# Inverter_New_2.net
KiCad netlist of a schematic drawn in EAGLE
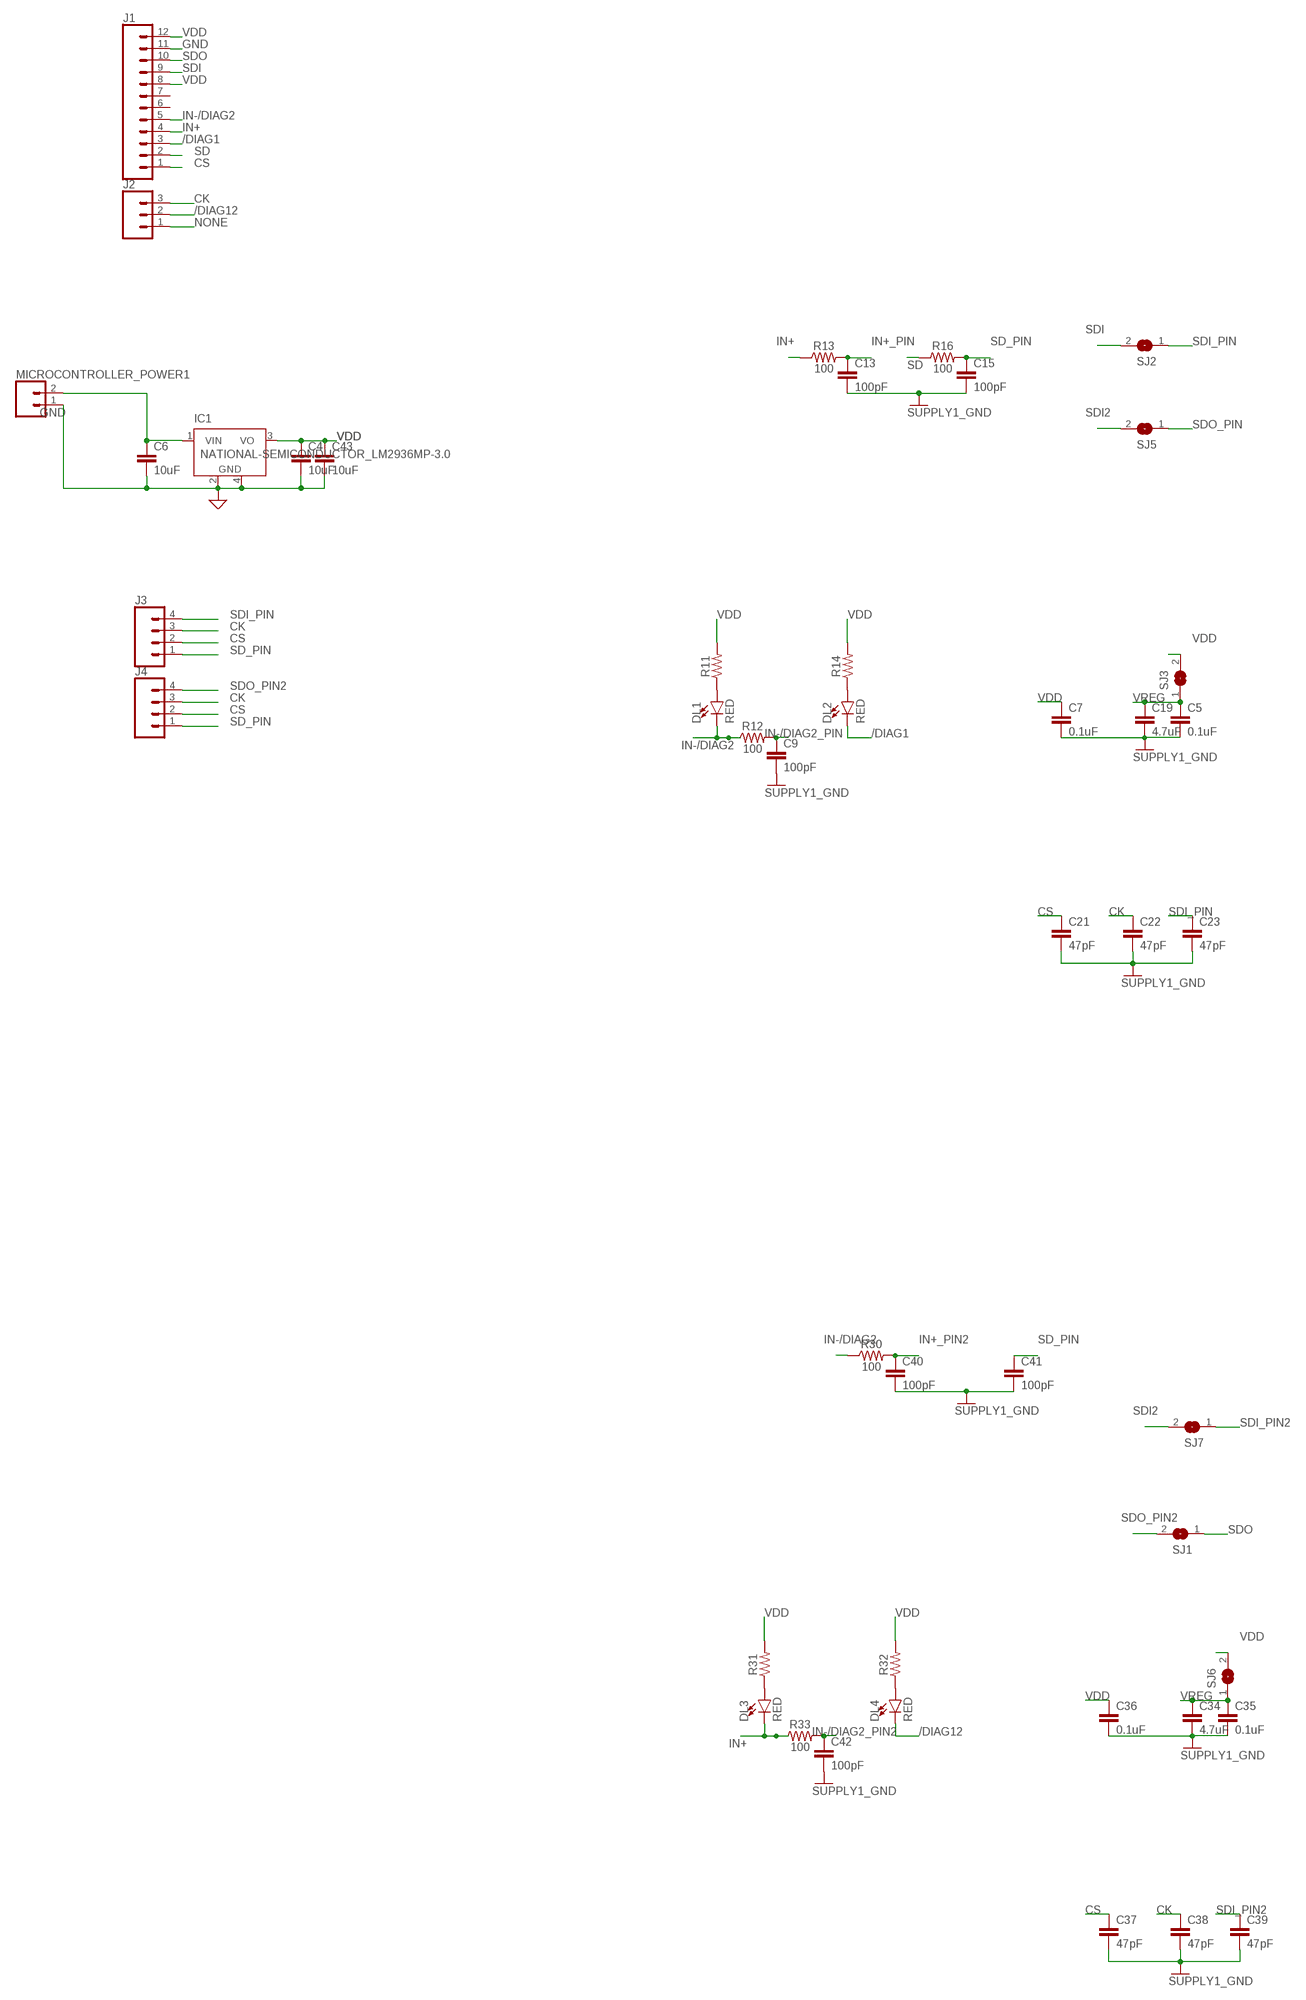
[diagram p0: schematic, sheet 1, part 1 of 2]
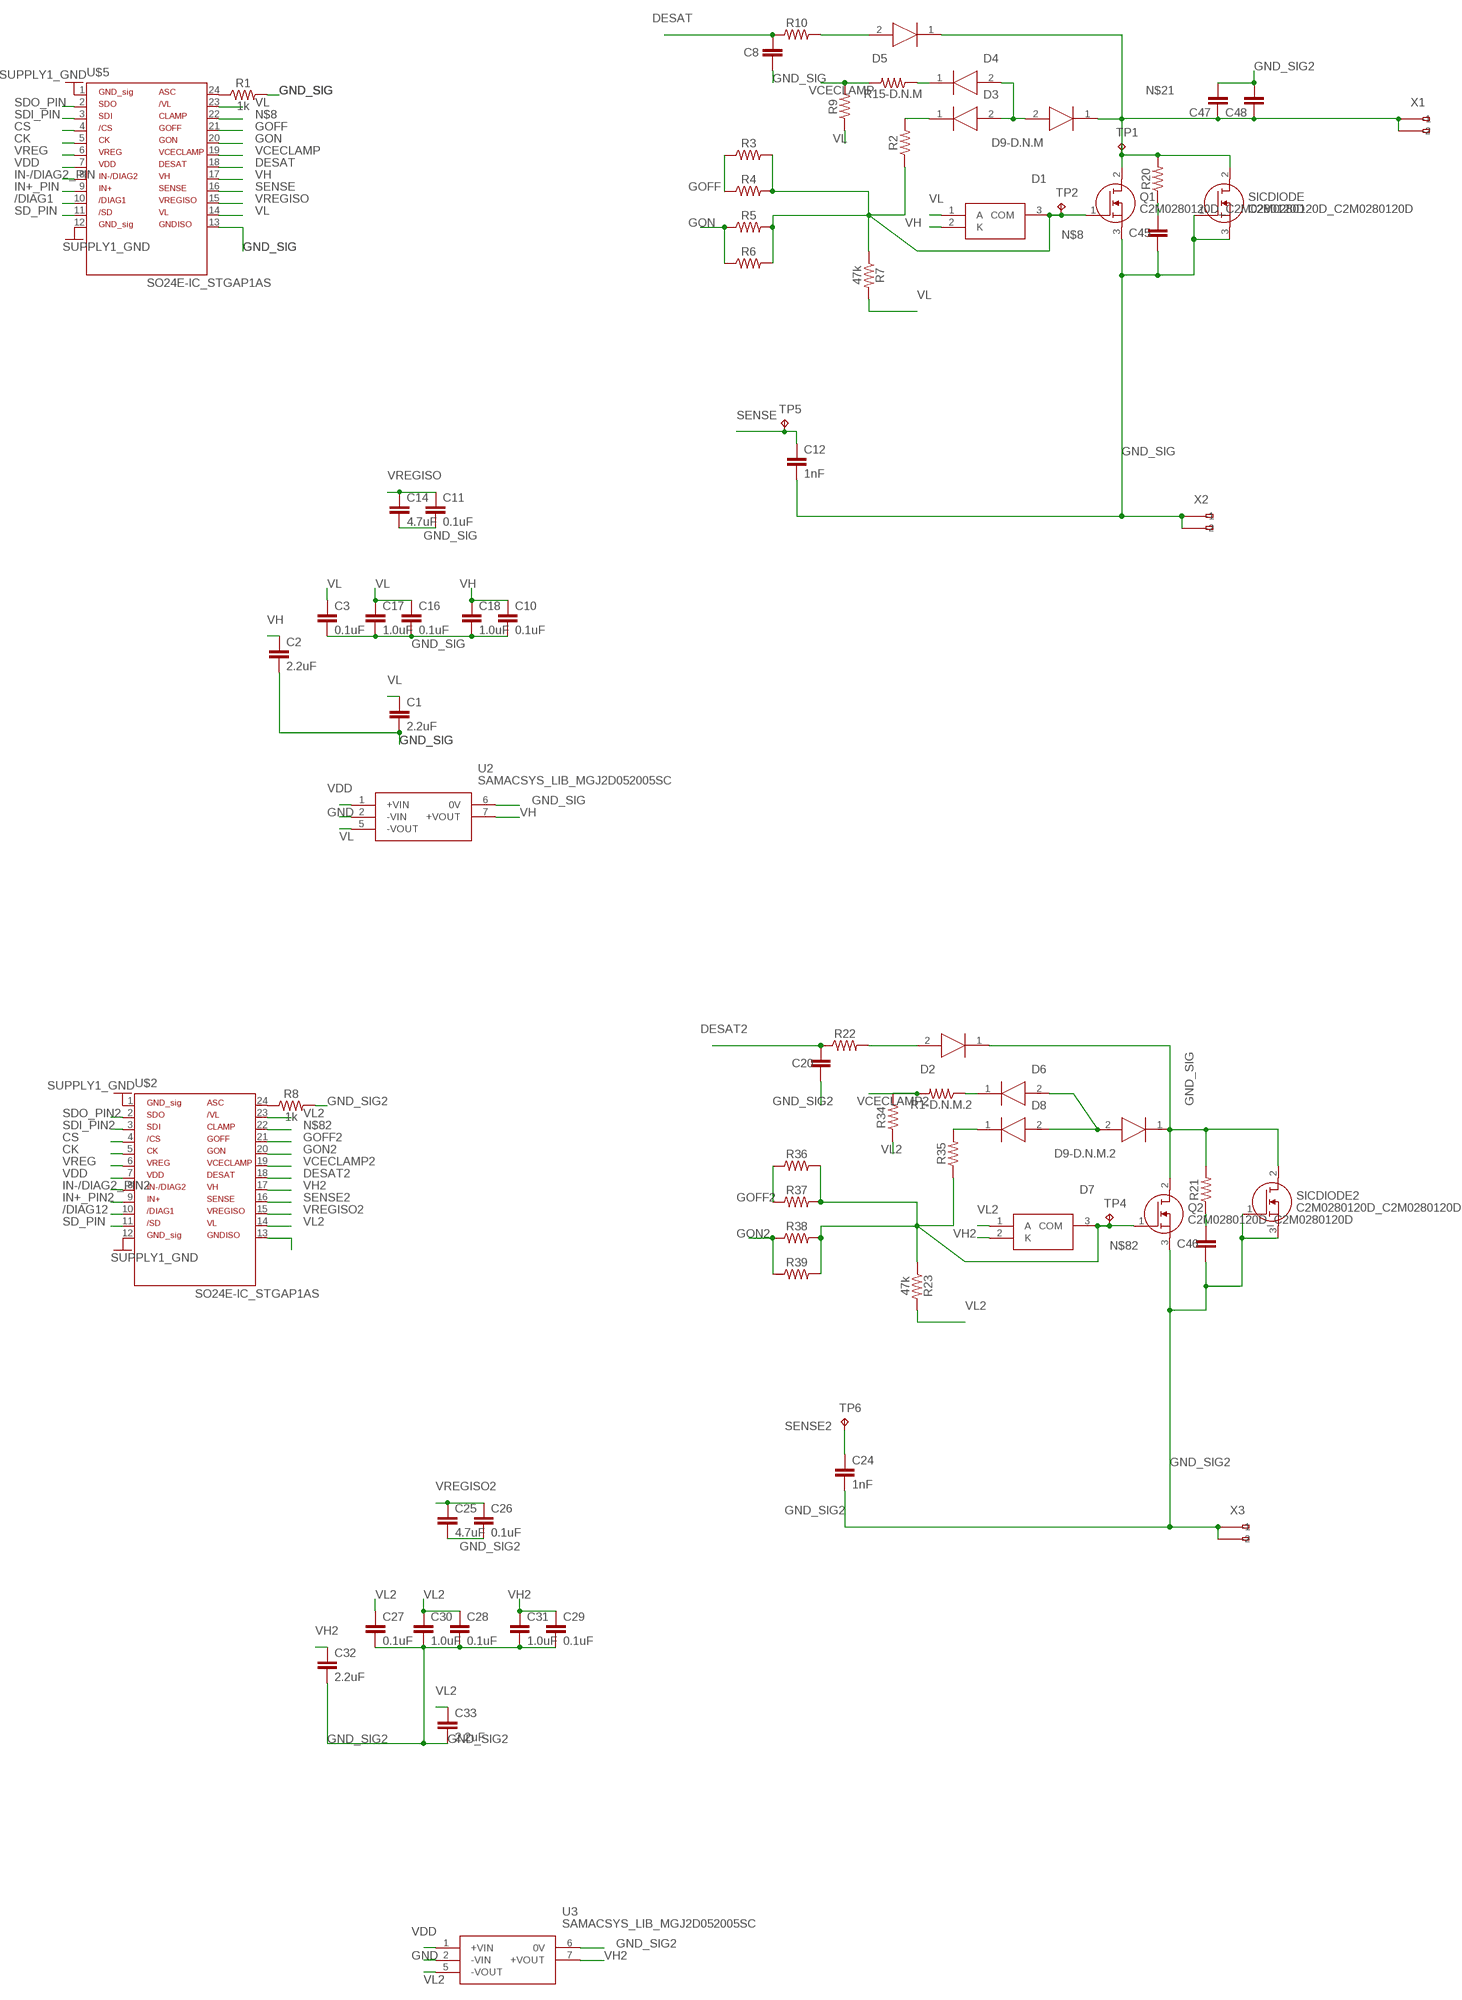
[diagram p1: schematic, sheet 1, part 2 of 2]
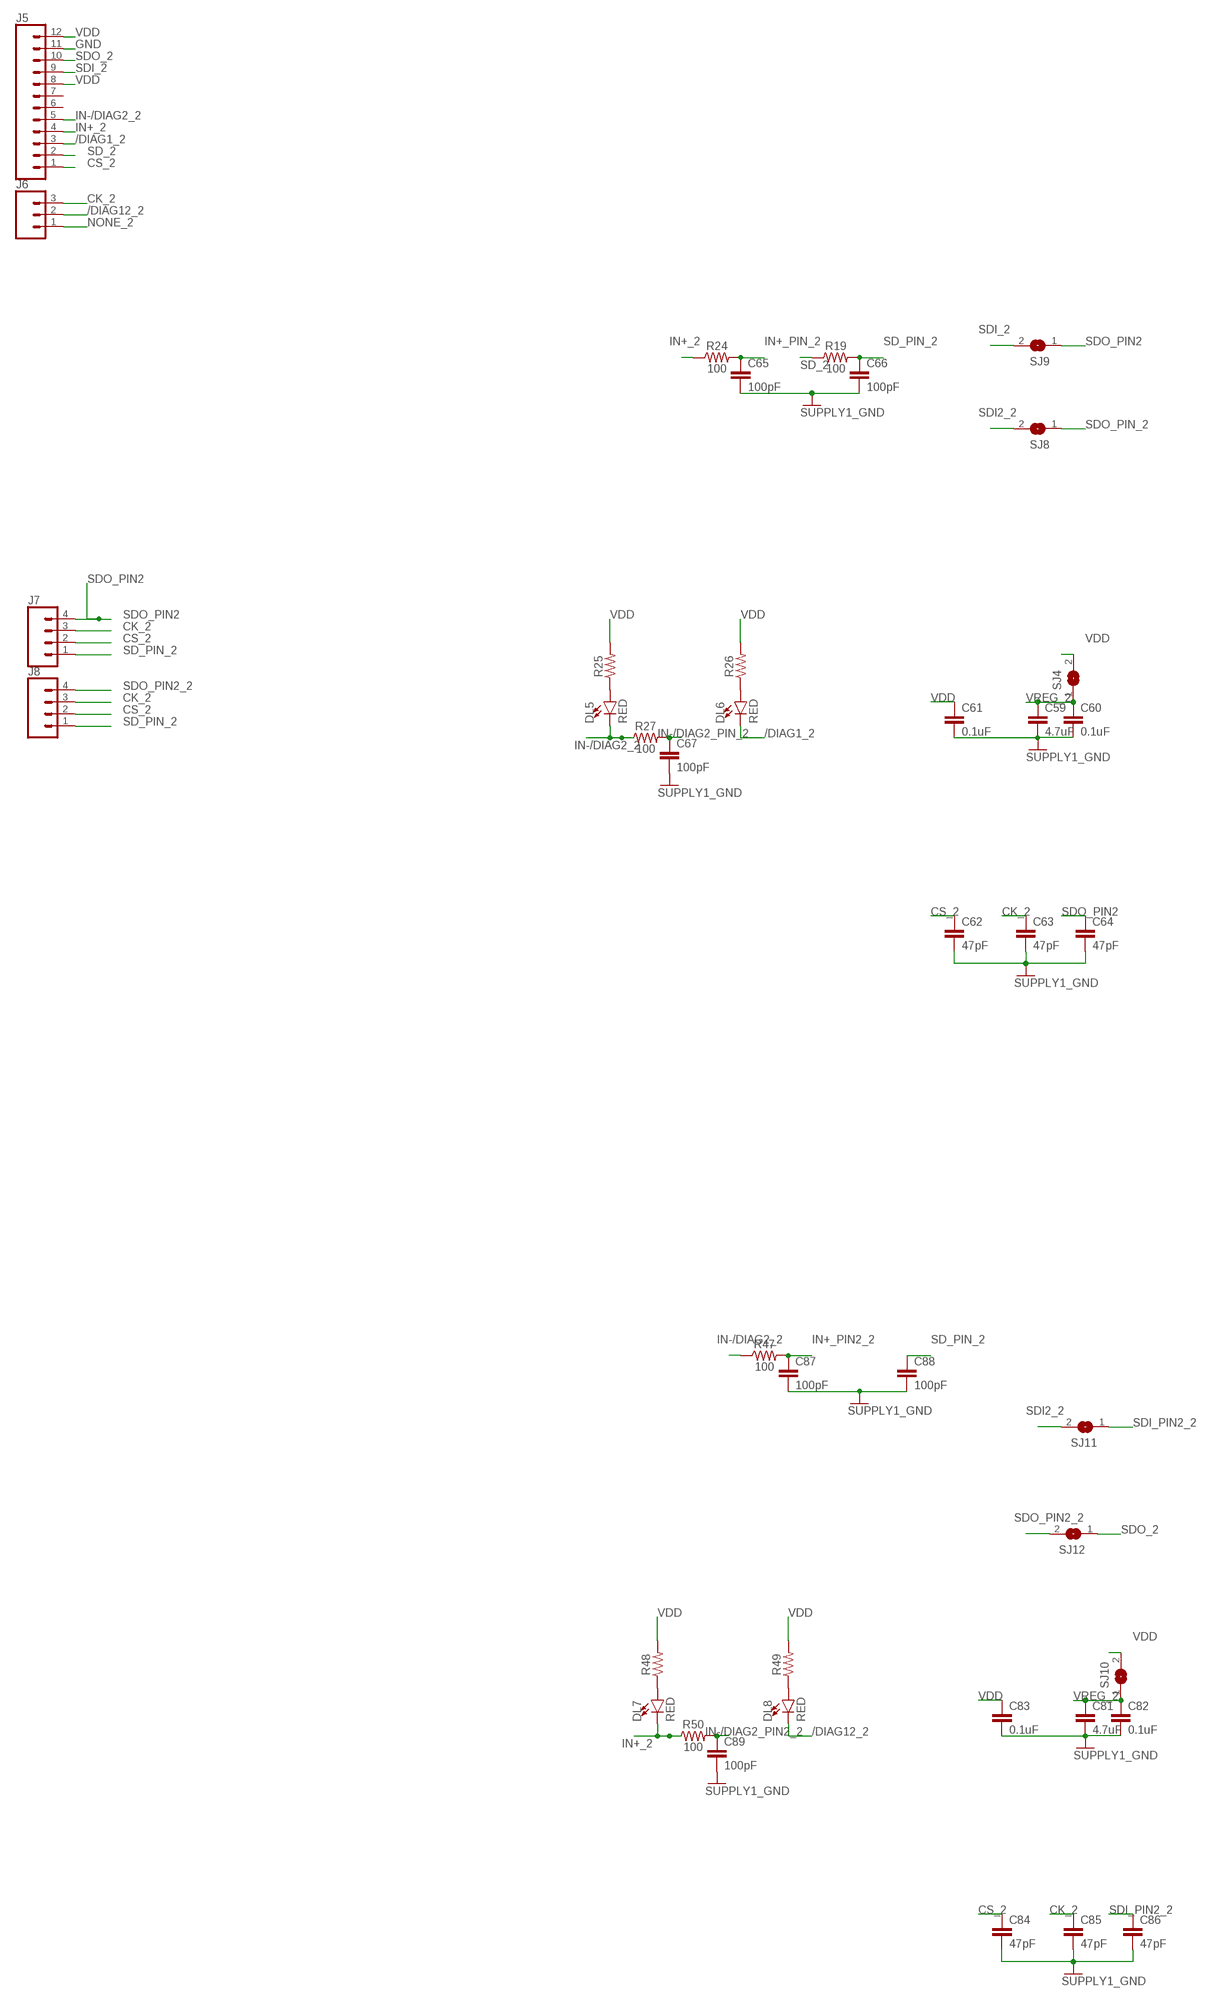
[diagram p2: schematic, sheet 2, part 1 of 2]
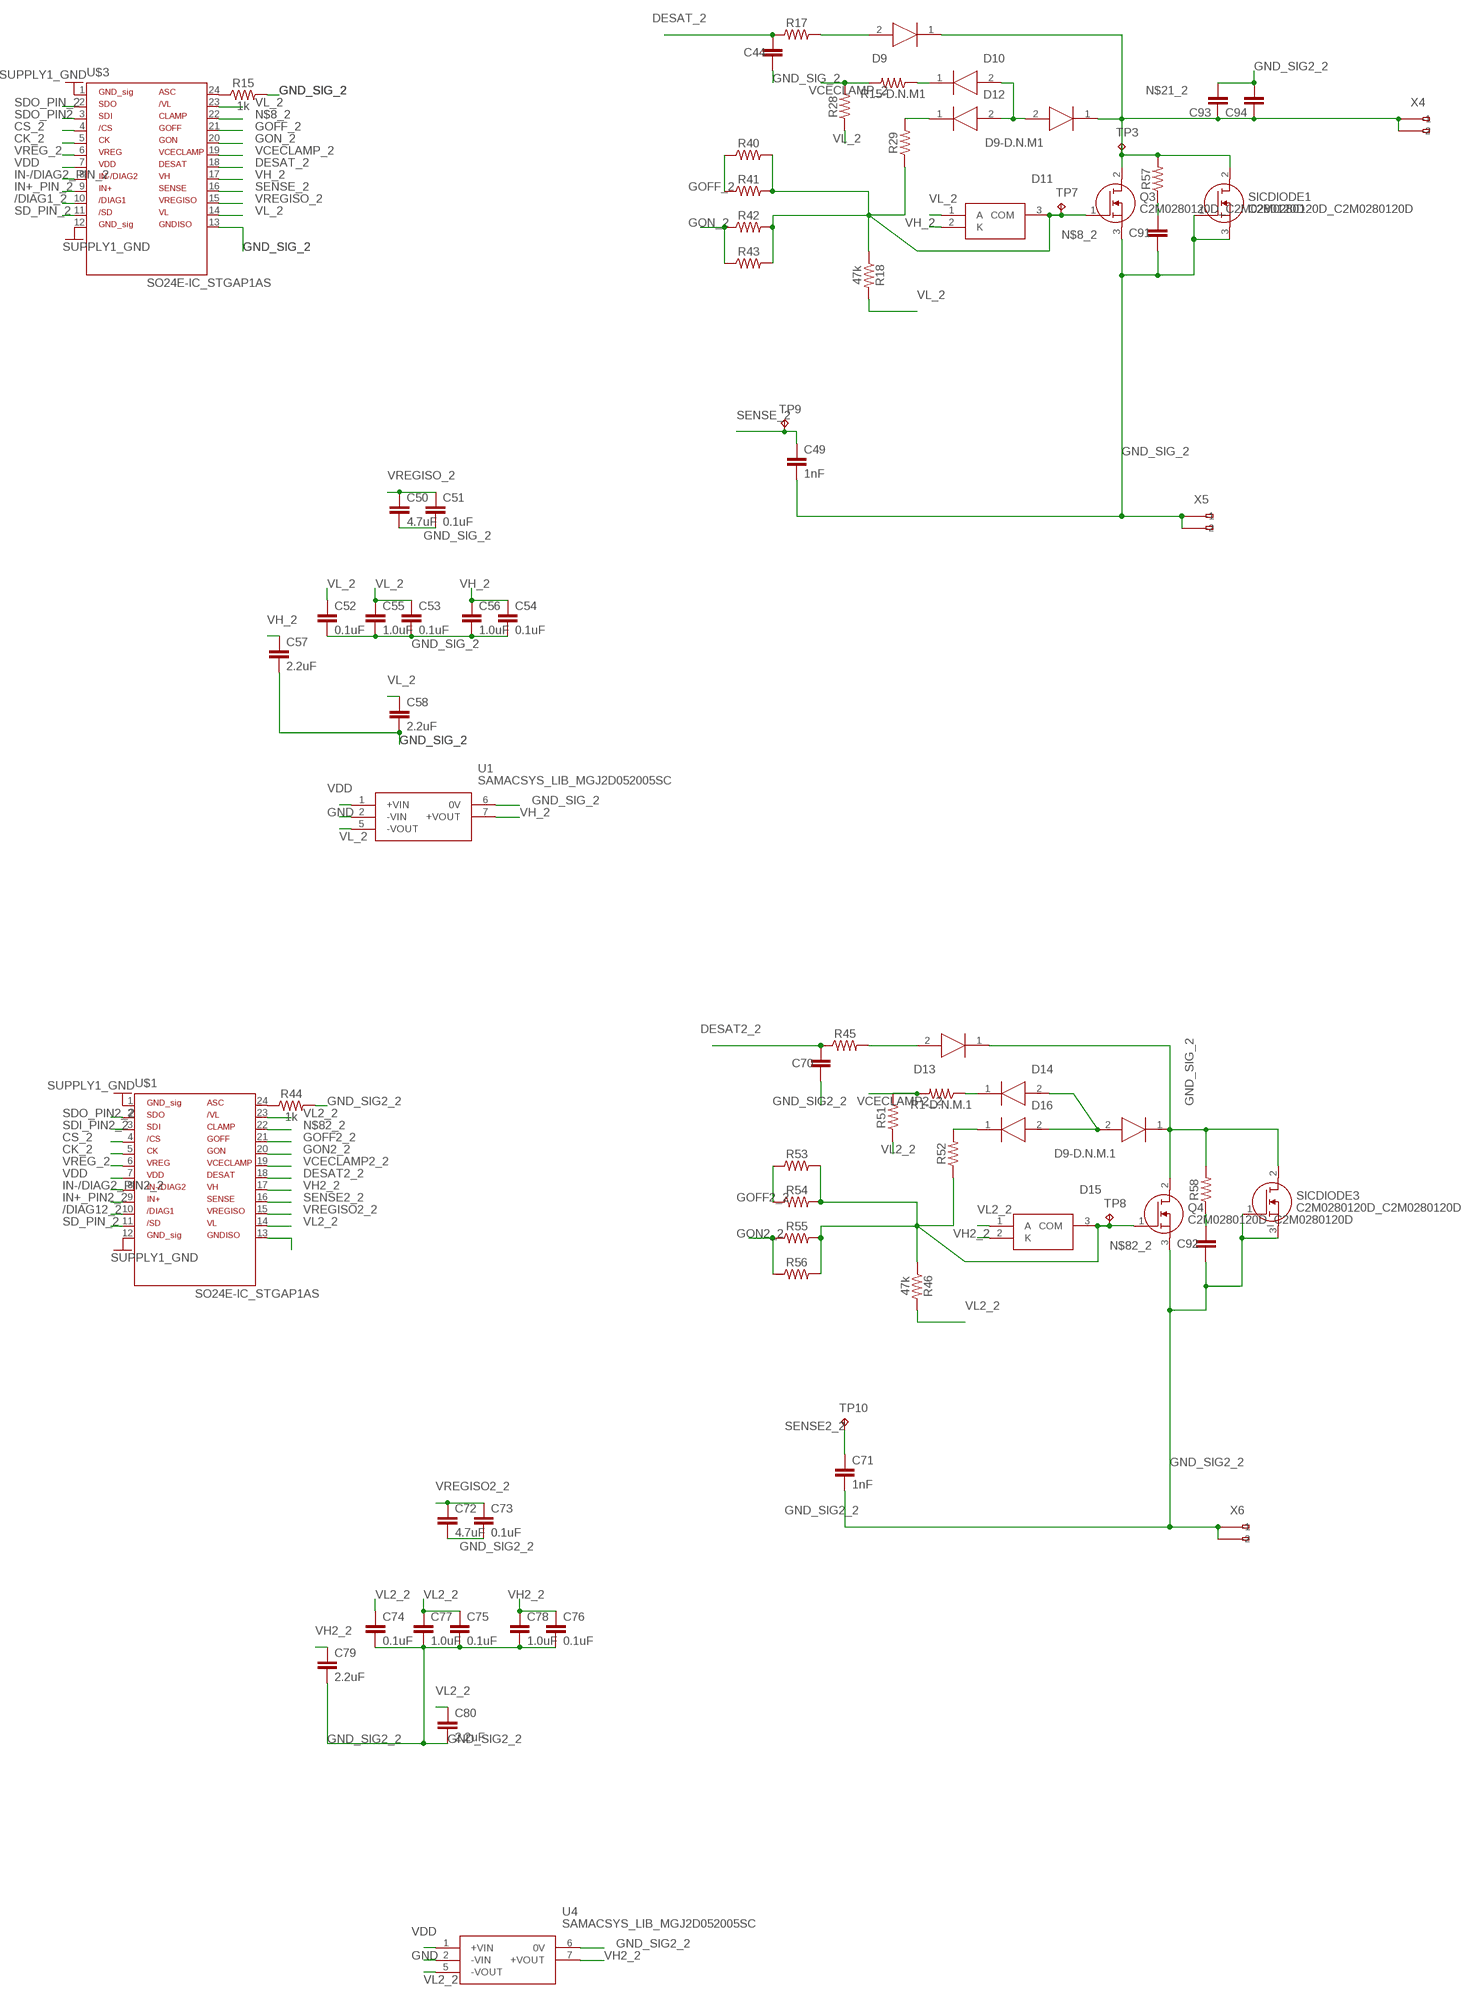
[diagram p3: schematic, sheet 2, part 2 of 2]
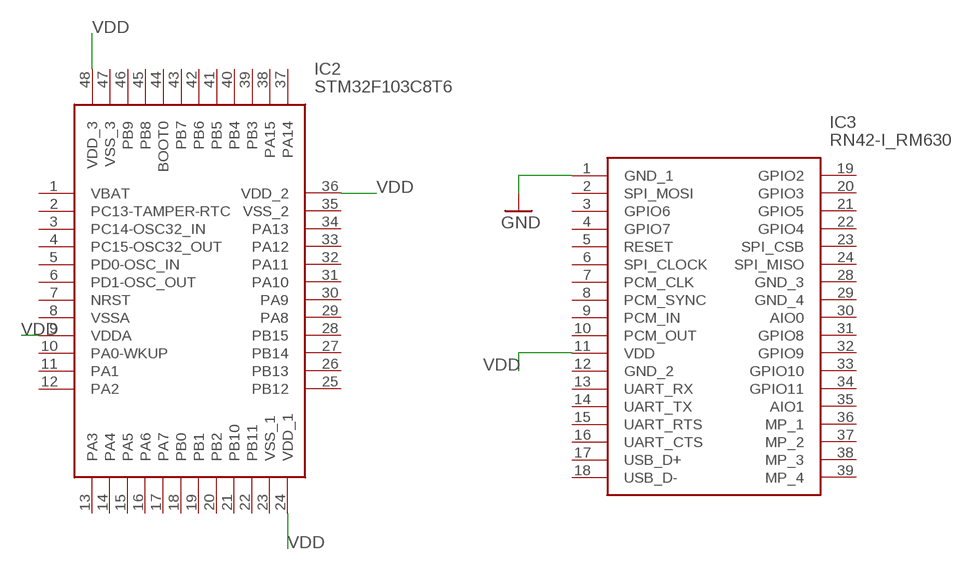
[diagram p4: schematic, sheet 3]

(export (version "E")
  (design (tool "Eeschema 10.0.6"))
  (components
    (comp (ref "IC2")
      (value "STM32F103C8T6")
      (footprint "eagle-import:QFP50P900X900X160-48N")
      (fields
        (field (name "MOUSER_PART_NUMBER") "511-STM32F103C8T6")
        (field (name "RS_PART_NUMBER") "0402279P")
      )
      (libsource (lib "eagle-import") (part "STM32F103C8T6"))
    )
    (comp (ref "IC3")
      (value "RN42-I_RM630")
      (footprint "eagle-import:RN42IRM630")
      (fields
        (field (name "MANUFACTURER_PART_NUMBER") "RN42-I/RM630")
        (field (name "MOUSER_PART_NUMBER") "579-RN42-I/RM630")
        (field (name "RS_PART_NUMBER") "1238533")
      )
      (libsource (lib "eagle-import") (part "RN42-I_RM630"))
    )
    (comp (ref "C44")
      (value "100pF")
      (footprint "eagle-import:SPARKFUN-CAPACITORS_0603")
      (libsource (lib "eagle-import") (part "SPARKFUN-CAPACITORS_100PF-0603-50V-5%"))
    )
    (comp (ref "C49")
      (value "1nF")
      (footprint "eagle-import:SPARKFUN-CAPACITORS_0603")
      (libsource (lib "eagle-import") (part "SPARKFUN-CAPACITORS_1.0NF/1000PF-0603-50V-10%"))
    )
    (comp (ref "C50")
      (value "4.7uF")
      (footprint "eagle-import:SPARKFUN-CAPACITORS_0603")
      (libsource (lib "eagle-import") (part "SPARKFUN-CAPACITORS_4.7UF0603"))
    )
    (comp (ref "C51")
      (value "0.1uF")
      (footprint "eagle-import:SPARKFUN-CAPACITORS_0603")
      (libsource (lib "eagle-import") (part "SPARKFUN-CAPACITORS_0.1UF-0603-100V-10%"))
    )
    (comp (ref "C52")
      (value "0.1uF")
      (footprint "eagle-import:SPARKFUN-CAPACITORS_0603")
      (libsource (lib "eagle-import") (part "SPARKFUN-CAPACITORS_0.1UF-0603-100V-10%"))
    )
    (comp (ref "C53")
      (value "0.1uF")
      (footprint "eagle-import:SPARKFUN-CAPACITORS_0603")
      (libsource (lib "eagle-import") (part "SPARKFUN-CAPACITORS_0.1UF-0603-100V-10%"))
    )
    (comp (ref "C54")
      (value "0.1uF")
      (footprint "eagle-import:SPARKFUN-CAPACITORS_0603")
      (libsource (lib "eagle-import") (part "SPARKFUN-CAPACITORS_0.1UF-0603-100V-10%"))
    )
    (comp (ref "C55")
      (value "1.0uF")
      (footprint "eagle-import:SPARKFUN-CAPACITORS_0805")
      (libsource (lib "eagle-import") (part "SPARKFUN-CAPACITORS_1.0UF-0805-25V-10%"))
    )
    (comp (ref "C56")
      (value "1.0uF")
      (footprint "eagle-import:SPARKFUN-CAPACITORS_0805")
      (libsource (lib "eagle-import") (part "SPARKFUN-CAPACITORS_1.0UF-0805-25V-10%"))
    )
    (comp (ref "C57")
      (value "2.2uF")
      (footprint "eagle-import:SPARKFUN-CAPACITORS_1206")
      (libsource (lib "eagle-import") (part "SPARKFUN-CAPACITORS_2.2UF-1206-50V-10%"))
    )
    (comp (ref "C58")
      (value "2.2uF")
      (footprint "eagle-import:SPARKFUN-CAPACITORS_1206")
      (libsource (lib "eagle-import") (part "SPARKFUN-CAPACITORS_2.2UF-1206-50V-10%"))
    )
    (comp (ref "C59")
      (value "4.7uF")
      (footprint "eagle-import:SPARKFUN-CAPACITORS_0603")
      (libsource (lib "eagle-import") (part "SPARKFUN-CAPACITORS_4.7UF0603"))
    )
    (comp (ref "C60")
      (value "0.1uF")
      (footprint "eagle-import:SPARKFUN-CAPACITORS_0603")
      (libsource (lib "eagle-import") (part "SPARKFUN-CAPACITORS_0.1UF-0603-100V-10%"))
    )
    (comp (ref "C61")
      (value "0.1uF")
      (footprint "eagle-import:SPARKFUN-CAPACITORS_0603")
      (libsource (lib "eagle-import") (part "SPARKFUN-CAPACITORS_0.1UF-0603-100V-10%"))
    )
    (comp (ref "C62")
      (value "47pF")
      (footprint "eagle-import:SPARKFUN-CAPACITORS_0603")
      (libsource (lib "eagle-import") (part "SPARKFUN-CAPACITORS_47PF-0603-50V-5%"))
    )
    (comp (ref "C63")
      (value "47pF")
      (footprint "eagle-import:SPARKFUN-CAPACITORS_0603")
      (libsource (lib "eagle-import") (part "SPARKFUN-CAPACITORS_47PF-0603-50V-5%"))
    )
    (comp (ref "C64")
      (value "47pF")
      (footprint "eagle-import:SPARKFUN-CAPACITORS_0603")
      (libsource (lib "eagle-import") (part "SPARKFUN-CAPACITORS_47PF-0603-50V-5%"))
    )
    (comp (ref "C65")
      (value "100pF")
      (footprint "eagle-import:SPARKFUN-CAPACITORS_0603")
      (libsource (lib "eagle-import") (part "SPARKFUN-CAPACITORS_100PF-0603-50V-5%"))
    )
    (comp (ref "C66")
      (value "100pF")
      (footprint "eagle-import:SPARKFUN-CAPACITORS_0603")
      (libsource (lib "eagle-import") (part "SPARKFUN-CAPACITORS_100PF-0603-50V-5%"))
    )
    (comp (ref "C67")
      (value "100pF")
      (footprint "eagle-import:SPARKFUN-CAPACITORS_0603")
      (libsource (lib "eagle-import") (part "SPARKFUN-CAPACITORS_100PF-0603-50V-5%"))
    )
    (comp (ref "C70")
      (value "100pF")
      (footprint "eagle-import:SPARKFUN-CAPACITORS_0603")
      (libsource (lib "eagle-import") (part "SPARKFUN-CAPACITORS_100PF-0603-50V-5%"))
    )
    (comp (ref "C71")
      (value "1nF")
      (footprint "eagle-import:SPARKFUN-CAPACITORS_0603")
      (libsource (lib "eagle-import") (part "SPARKFUN-CAPACITORS_1.0NF/1000PF-0603-50V-10%"))
    )
    (comp (ref "C72")
      (value "4.7uF")
      (footprint "eagle-import:SPARKFUN-CAPACITORS_0603")
      (libsource (lib "eagle-import") (part "SPARKFUN-CAPACITORS_4.7UF0603"))
    )
    (comp (ref "C73")
      (value "0.1uF")
      (footprint "eagle-import:SPARKFUN-CAPACITORS_0603")
      (libsource (lib "eagle-import") (part "SPARKFUN-CAPACITORS_0.1UF-0603-100V-10%"))
    )
    (comp (ref "C74")
      (value "0.1uF")
      (footprint "eagle-import:SPARKFUN-CAPACITORS_0603")
      (libsource (lib "eagle-import") (part "SPARKFUN-CAPACITORS_0.1UF-0603-100V-10%"))
    )
    (comp (ref "C75")
      (value "0.1uF")
      (footprint "eagle-import:SPARKFUN-CAPACITORS_0603")
      (libsource (lib "eagle-import") (part "SPARKFUN-CAPACITORS_0.1UF-0603-100V-10%"))
    )
    (comp (ref "C76")
      (value "0.1uF")
      (footprint "eagle-import:SPARKFUN-CAPACITORS_0603")
      (libsource (lib "eagle-import") (part "SPARKFUN-CAPACITORS_0.1UF-0603-100V-10%"))
    )
    (comp (ref "C77")
      (value "1.0uF")
      (footprint "eagle-import:SPARKFUN-CAPACITORS_0805")
      (libsource (lib "eagle-import") (part "SPARKFUN-CAPACITORS_1.0UF-0805-25V-10%"))
    )
    (comp (ref "C78")
      (value "1.0uF")
      (footprint "eagle-import:SPARKFUN-CAPACITORS_0805")
      (libsource (lib "eagle-import") (part "SPARKFUN-CAPACITORS_1.0UF-0805-25V-10%"))
    )
    (comp (ref "C79")
      (value "2.2uF")
      (footprint "eagle-import:SPARKFUN-CAPACITORS_1206")
      (fields (field (name "SPICEPREFIX") "C"))
      (libsource (lib "eagle-import") (part "SPARKFUN-CAPACITORS_2.2UF-1206-50V-10%"))
    )
    (comp (ref "C80")
      (value "2.2uF")
      (footprint "eagle-import:SPARKFUN-CAPACITORS_1206")
      (libsource (lib "eagle-import") (part "SPARKFUN-CAPACITORS_2.2UF-1206-50V-10%"))
    )
    (comp (ref "C81")
      (value "4.7uF")
      (footprint "eagle-import:SPARKFUN-CAPACITORS_0603")
      (libsource (lib "eagle-import") (part "SPARKFUN-CAPACITORS_4.7UF0603"))
    )
    (comp (ref "C82")
      (value "0.1uF")
      (footprint "eagle-import:SPARKFUN-CAPACITORS_0603")
      (libsource (lib "eagle-import") (part "SPARKFUN-CAPACITORS_0.1UF-0603-100V-10%"))
    )
    (comp (ref "C83")
      (value "0.1uF")
      (footprint "eagle-import:SPARKFUN-CAPACITORS_0603")
      (libsource (lib "eagle-import") (part "SPARKFUN-CAPACITORS_0.1UF-0603-100V-10%"))
    )
    (comp (ref "C84")
      (value "47pF")
      (footprint "eagle-import:SPARKFUN-CAPACITORS_0603")
      (libsource (lib "eagle-import") (part "SPARKFUN-CAPACITORS_47PF-0603-50V-5%"))
    )
    (comp (ref "C85")
      (value "47pF")
      (footprint "eagle-import:SPARKFUN-CAPACITORS_0603")
      (libsource (lib "eagle-import") (part "SPARKFUN-CAPACITORS_47PF-0603-50V-5%"))
    )
    (comp (ref "C86")
      (value "47pF")
      (footprint "eagle-import:SPARKFUN-CAPACITORS_0603")
      (libsource (lib "eagle-import") (part "SPARKFUN-CAPACITORS_47PF-0603-50V-5%"))
    )
    (comp (ref "C87")
      (value "100pF")
      (footprint "eagle-import:SPARKFUN-CAPACITORS_0603")
      (libsource (lib "eagle-import") (part "SPARKFUN-CAPACITORS_100PF-0603-50V-5%"))
    )
    (comp (ref "C88")
      (value "100pF")
      (footprint "eagle-import:SPARKFUN-CAPACITORS_0603")
      (libsource (lib "eagle-import") (part "SPARKFUN-CAPACITORS_100PF-0603-50V-5%"))
    )
    (comp (ref "C89")
      (value "100pF")
      (footprint "eagle-import:SPARKFUN-CAPACITORS_0603")
      (libsource (lib "eagle-import") (part "SPARKFUN-CAPACITORS_100PF-0603-50V-5%"))
    )
    (comp (ref "C91")
      (value "100pF")
      (footprint "eagle-import:SPARKFUN-CAPACITORS_0603")
      (libsource (lib "eagle-import") (part "SPARKFUN-CAPACITORS_100PF-0603-50V-5%"))
    )
    (comp (ref "C92")
      (value "100pF")
      (footprint "eagle-import:SPARKFUN-CAPACITORS_0603")
      (libsource (lib "eagle-import") (part "SPARKFUN-CAPACITORS_100PF-0603-50V-5%"))
    )
    (comp (ref "C93")
      (value "C-EU225-062X268")
      (footprint "eagle-import:C225-062X268")
      (libsource (lib "eagle-import") (part "C-EU225-062X268"))
    )
    (comp (ref "C94")
      (value "C-EU225-062X268")
      (footprint "eagle-import:C225-062X268")
      (libsource (lib "eagle-import") (part "C-EU225-062X268"))
    )
    (comp (ref "D9")
      (value "STTH112A_STTH112A")
      (footprint "eagle-import:STTH112A_DIOM5126X265N")
      (fields (field (name "MANUFACTURER_PART_NUMBER") "STTH112A") (field (name "RS_PART_NUMBER") "0249319"))
      (libsource (lib "eagle-import") (part "STTH112A_STTH112A"))
    )
    (comp (ref "D9-D.N.M.1")
      (value "STPS2H100A_STPS2H100A")
      (footprint "eagle-import:STPS2H100A_DIOM5126X265N")
      (fields
        (field (name "MANUFACTURER_PART_NUMBER") "STPS2H100A")
        (field (name "RS_PART_NUMBER") "0249612P")
        (field (name "SPICEPREFIX") "D")
      )
      (libsource (lib "eagle-import") (part "STPS2H100A_STPS2H100A"))
    )
    (comp (ref "D9-D.N.M1")
      (value "STPS2H100A_STPS2H100A")
      (footprint "eagle-import:STPS2H100A_DIOM5126X265N")
      (fields
        (field (name "MANUFACTURER_PART_NUMBER") "STPS2H100A")
        (field (name "RS_PART_NUMBER") "0249612P")
      )
      (libsource (lib "eagle-import") (part "STPS2H100A_STPS2H100A"))
    )
    (comp (ref "D10")
      (value "BAT20JFILM_BAT20JFILM")
      (footprint "eagle-import:BAT20JFILM_SOD2512X113N")
      (fields
        (field (name "MANUFACTURER_PART_NUMBER") "BAT20JFILM")
        (field (name "RS_PART_NUMBER") "1657545")
      )
      (libsource (lib "eagle-import") (part "BAT20JFILM_BAT20JFILM"))
    )
    (comp (ref "D11")
      (value "BAT54SFILM_BAT54SFILM")
      (footprint "eagle-import:BAT54SFILM_SOT105P242X150-3N")
      (fields
        (field (name "MANUFACTURER_PART_NUMBER") "BAT54SFILM")
        (field (name "RS_PART_NUMBER") "7146863P")
      )
      (libsource (lib "eagle-import") (part "BAT54SFILM_BAT54SFILM"))
    )
    (comp (ref "D12")
      (value "STPS2H100A_STPS2H100A")
      (footprint "eagle-import:STPS2H100A_DIOM5126X265N")
      (fields
        (field (name "MANUFACTURER_PART_NUMBER") "STPS2H100A")
        (field (name "RS_PART_NUMBER") "0249612P")
      )
      (libsource (lib "eagle-import") (part "STPS2H100A_STPS2H100A"))
    )
    (comp (ref "D13")
      (value "STTH112A_STTH112A")
      (footprint "eagle-import:STTH112A_DIOM5126X265N")
      (fields (field (name "MANUFACTURER_PART_NUMBER") "STTH112A") (field (name "RS_PART_NUMBER") "0249319"))
      (libsource (lib "eagle-import") (part "STTH112A_STTH112A"))
    )
    (comp (ref "D14")
      (value "BAT20JFILM_BAT20JFILM")
      (footprint "eagle-import:BAT20JFILM_SOD2512X113N")
      (fields
        (field (name "MANUFACTURER_PART_NUMBER") "BAT20JFILM")
        (field (name "RS_PART_NUMBER") "1657545")
      )
      (libsource (lib "eagle-import") (part "BAT20JFILM_BAT20JFILM"))
    )
    (comp (ref "D15")
      (value "BAT54SFILM_BAT54SFILM")
      (footprint "eagle-import:BAT54SFILM_SOT105P242X150-3N")
      (fields
        (field (name "MANUFACTURER_PART_NUMBER") "BAT54SFILM")
        (field (name "RS_PART_NUMBER") "7146863P")
        (field (name "SPICEPREFIX") "J")
      )
      (libsource (lib "eagle-import") (part "BAT54SFILM_BAT54SFILM"))
    )
    (comp (ref "D16")
      (value "STPS2H100A_STPS2H100A")
      (footprint "eagle-import:STPS2H100A_DIOM5126X265N")
      (fields
        (field (name "MANUFACTURER_PART_NUMBER") "STPS2H100A")
        (field (name "RS_PART_NUMBER") "0249612P")
        (field (name "SPICEPREFIX") "D")
      )
      (libsource (lib "eagle-import") (part "STPS2H100A_STPS2H100A"))
    )
    (comp (ref "DL5")
      (value "RED")
      (footprint "eagle-import:SPARKFUN-LED_LED-1206")
      (libsource (lib "eagle-import") (part "SPARKFUN-LED_LED-RED1206"))
    )
    (comp (ref "DL6")
      (value "RED")
      (footprint "eagle-import:SPARKFUN-LED_LED-1206")
      (libsource (lib "eagle-import") (part "SPARKFUN-LED_LED-RED1206"))
    )
    (comp (ref "DL7")
      (value "RED")
      (footprint "eagle-import:SPARKFUN-LED_LED-1206")
      (libsource (lib "eagle-import") (part "SPARKFUN-LED_LED-RED1206"))
    )
    (comp (ref "DL8")
      (value "RED")
      (footprint "eagle-import:SPARKFUN-LED_LED-1206")
      (libsource (lib "eagle-import") (part "SPARKFUN-LED_LED-RED1206"))
    )
    (comp (ref "J5")
      (value "SPARKFUN-CONNECTORS_CONN_12LONGPADS")
      (footprint "eagle-import:SPARKFUN-CONNECTORS_1X12_LONGPADS")
      (libsource (lib "eagle-import") (part "SPARKFUN-CONNECTORS_CONN_12LONGPADS"))
    )
    (comp (ref "J6")
      (value "SPARKFUN-CONNECTORS_CONN_03LONGPADS")
      (footprint "eagle-import:SPARKFUN-CONNECTORS_1X03_LONGPADS")
      (libsource (lib "eagle-import") (part "SPARKFUN-CONNECTORS_CONN_03LONGPADS"))
    )
    (comp (ref "J7")
      (value "SPARKFUN-CONNECTORS_CONN_04LONGPADS")
      (footprint "eagle-import:SPARKFUN-CONNECTORS_1X04_LONGPADS")
      (libsource (lib "eagle-import") (part "SPARKFUN-CONNECTORS_CONN_04LONGPADS"))
    )
    (comp (ref "J8")
      (value "SPARKFUN-CONNECTORS_CONN_04LONGPADS")
      (footprint "eagle-import:SPARKFUN-CONNECTORS_1X04_LONGPADS")
      (libsource (lib "eagle-import") (part "SPARKFUN-CONNECTORS_CONN_04LONGPADS"))
    )
    (comp (ref "Q3")
      (value "C2M0280120D_C2M0280120D")
      (footprint "eagle-import:C2M0280120D_TO544P521X1594X2550-3P")
      (fields
        (field (name "MANUFACTURER_PART_NUMBER") "C2M0280120D")
        (field (name "RS_PART_NUMBER") "9158820P")
      )
      (libsource (lib "eagle-import") (part "C2M0280120D_C2M0280120D"))
    )
    (comp (ref "Q4")
      (value "C2M0280120D_C2M0280120D")
      (footprint "eagle-import:C2M0280120D_TO544P521X1594X2550-3P")
      (fields
        (field (name "MANUFACTURER_PART_NUMBER") "C2M0280120D")
        (field (name "RS_PART_NUMBER") "9158820P")
      )
      (libsource (lib "eagle-import") (part "C2M0280120D_C2M0280120D"))
    )
    (comp (ref "R1-D.N.M.1")
      (value "0")
      (footprint "eagle-import:SPARKFUN-RESISTORS_0603")
      (libsource (lib "eagle-import") (part "SPARKFUN-RESISTORS_0OHM-0603-1/10W-5%"))
    )
    (comp (ref "R15")
      (value "1k")
      (footprint "eagle-import:SPARKFUN-RESISTORS_0603")
      (libsource (lib "eagle-import") (part "SPARKFUN-RESISTORS_1KOHM-0603-1/10W-1%"))
    )
    (comp (ref "R15-D.N.M1")
      (value "0")
      (footprint "eagle-import:SPARKFUN-RESISTORS_0603")
      (libsource (lib "eagle-import") (part "SPARKFUN-RESISTORS_0OHM-0603-1/10W-5%"))
    )
    (comp (ref "R17")
      (value "1k")
      (footprint "eagle-import:SPARKFUN-RESISTORS_0603")
      (libsource (lib "eagle-import") (part "SPARKFUN-RESISTORS_1KOHM-0603-1/10W-1%"))
    )
    (comp (ref "R18")
      (value "47k")
      (footprint "eagle-import:SPARKFUN-RESISTORS_0603")
      (libsource (lib "eagle-import") (part "SPARKFUN-RESISTORS_47KOHM-0603-1/10W-1%"))
    )
    (comp (ref "R19")
      (value "100")
      (footprint "eagle-import:SPARKFUN-RESISTORS_0603")
      (libsource (lib "eagle-import") (part "SPARKFUN-RESISTORS_100OHM-0603-1/4W-5%"))
    )
    (comp (ref "R24")
      (value "100")
      (footprint "eagle-import:SPARKFUN-RESISTORS_0603")
      (libsource (lib "eagle-import") (part "SPARKFUN-RESISTORS_100OHM-0603-1/4W-5%"))
    )
    (comp (ref "R25")
      (value "SPARKFUN-RESISTORS_RESISTOR0603")
      (footprint "eagle-import:SPARKFUN-RESISTORS_0603")
      (libsource (lib "eagle-import") (part "SPARKFUN-RESISTORS_RESISTOR0603"))
    )
    (comp (ref "R26")
      (value "SPARKFUN-RESISTORS_RESISTOR0603")
      (footprint "eagle-import:SPARKFUN-RESISTORS_0603")
      (libsource (lib "eagle-import") (part "SPARKFUN-RESISTORS_RESISTOR0603"))
    )
    (comp (ref "R27")
      (value "100")
      (footprint "eagle-import:SPARKFUN-RESISTORS_0603")
      (libsource (lib "eagle-import") (part "SPARKFUN-RESISTORS_100OHM-0603-1/4W-5%"))
    )
    (comp (ref "R28")
      (value "0")
      (footprint "eagle-import:SPARKFUN-RESISTORS_0603")
      (libsource (lib "eagle-import") (part "SPARKFUN-RESISTORS_0OHM-0603-1/10W-5%"))
    )
    (comp (ref "R29")
      (value "SPARKFUN-RESISTORS_RESISTOR0805")
      (footprint "eagle-import:SPARKFUN-RESISTORS_0805")
      (libsource (lib "eagle-import") (part "SPARKFUN-RESISTORS_RESISTOR0805"))
    )
    (comp (ref "R40")
      (value "SPARKFUN-RESISTORS_RESISTOR1206")
      (footprint "eagle-import:SPARKFUN-RESISTORS_1206")
      (libsource (lib "eagle-import") (part "SPARKFUN-RESISTORS_RESISTOR1206"))
    )
    (comp (ref "R41")
      (value "SPARKFUN-RESISTORS_RESISTOR1206")
      (footprint "eagle-import:SPARKFUN-RESISTORS_1206")
      (libsource (lib "eagle-import") (part "SPARKFUN-RESISTORS_RESISTOR1206"))
    )
    (comp (ref "R42")
      (value "SPARKFUN-RESISTORS_RESISTOR1206")
      (footprint "eagle-import:SPARKFUN-RESISTORS_1206")
      (libsource (lib "eagle-import") (part "SPARKFUN-RESISTORS_RESISTOR1206"))
    )
    (comp (ref "R43")
      (value "SPARKFUN-RESISTORS_RESISTOR1206")
      (footprint "eagle-import:SPARKFUN-RESISTORS_1206")
      (libsource (lib "eagle-import") (part "SPARKFUN-RESISTORS_RESISTOR1206"))
    )
    (comp (ref "R44")
      (value "1k")
      (footprint "eagle-import:SPARKFUN-RESISTORS_0603")
      (libsource (lib "eagle-import") (part "SPARKFUN-RESISTORS_1KOHM-0603-1/10W-1%"))
    )
    (comp (ref "R45")
      (value "1k")
      (footprint "eagle-import:SPARKFUN-RESISTORS_0603")
      (libsource (lib "eagle-import") (part "SPARKFUN-RESISTORS_1KOHM-0603-1/10W-1%"))
    )
    (comp (ref "R46")
      (value "47k")
      (footprint "eagle-import:SPARKFUN-RESISTORS_0603")
      (libsource (lib "eagle-import") (part "SPARKFUN-RESISTORS_47KOHM-0603-1/10W-1%"))
    )
    (comp (ref "R47")
      (value "100")
      (footprint "eagle-import:SPARKFUN-RESISTORS_0603")
      (libsource (lib "eagle-import") (part "SPARKFUN-RESISTORS_100OHM-0603-1/4W-5%"))
    )
    (comp (ref "R48")
      (value "SPARKFUN-RESISTORS_RESISTOR0603")
      (footprint "eagle-import:SPARKFUN-RESISTORS_0603")
      (libsource (lib "eagle-import") (part "SPARKFUN-RESISTORS_RESISTOR0603"))
    )
    (comp (ref "R49")
      (value "SPARKFUN-RESISTORS_RESISTOR0603")
      (footprint "eagle-import:SPARKFUN-RESISTORS_0603")
      (libsource (lib "eagle-import") (part "SPARKFUN-RESISTORS_RESISTOR0603"))
    )
    (comp (ref "R50")
      (value "100")
      (footprint "eagle-import:SPARKFUN-RESISTORS_0603")
      (libsource (lib "eagle-import") (part "SPARKFUN-RESISTORS_100OHM-0603-1/4W-5%"))
    )
    (comp (ref "R51")
      (value "0")
      (footprint "eagle-import:SPARKFUN-RESISTORS_0603")
      (libsource (lib "eagle-import") (part "SPARKFUN-RESISTORS_0OHM-0603-1/10W-5%"))
    )
    (comp (ref "R52")
      (value "SPARKFUN-RESISTORS_RESISTOR0805")
      (footprint "eagle-import:SPARKFUN-RESISTORS_0805")
      (libsource (lib "eagle-import") (part "SPARKFUN-RESISTORS_RESISTOR0805"))
    )
    (comp (ref "R53")
      (value "SPARKFUN-RESISTORS_RESISTOR1206")
      (footprint "eagle-import:SPARKFUN-RESISTORS_1206")
      (libsource (lib "eagle-import") (part "SPARKFUN-RESISTORS_RESISTOR1206"))
    )
    (comp (ref "R54")
      (value "SPARKFUN-RESISTORS_RESISTOR1206")
      (footprint "eagle-import:SPARKFUN-RESISTORS_1206")
      (libsource (lib "eagle-import") (part "SPARKFUN-RESISTORS_RESISTOR1206"))
    )
    (comp (ref "R55")
      (value "SPARKFUN-RESISTORS_RESISTOR1206")
      (footprint "eagle-import:SPARKFUN-RESISTORS_1206")
      (libsource (lib "eagle-import") (part "SPARKFUN-RESISTORS_RESISTOR1206"))
    )
    (comp (ref "R56")
      (value "SPARKFUN-RESISTORS_RESISTOR1206")
      (footprint "eagle-import:SPARKFUN-RESISTORS_1206")
      (libsource (lib "eagle-import") (part "SPARKFUN-RESISTORS_RESISTOR1206"))
    )
    (comp (ref "R57")
      (value "SPARKFUN-RESISTORS_RESISTOR1206")
      (footprint "eagle-import:SPARKFUN-RESISTORS_1206")
      (libsource (lib "eagle-import") (part "SPARKFUN-RESISTORS_RESISTOR1206"))
    )
    (comp (ref "R58")
      (value "SPARKFUN-RESISTORS_RESISTOR1206")
      (footprint "eagle-import:SPARKFUN-RESISTORS_1206")
      (libsource (lib "eagle-import") (part "SPARKFUN-RESISTORS_RESISTOR1206"))
    )
    (comp (ref "SICDIODE1")
      (value "C2M0280120D_C2M0280120D")
      (footprint "eagle-import:C2M0280120D_TO544P521X1594X2550-3P")
      (fields
        (field (name "MANUFACTURER_PART_NUMBER") "C2M0280120D")
        (field (name "RS_PART_NUMBER") "9158820P")
      )
      (libsource (lib "eagle-import") (part "C2M0280120D_C2M0280120D"))
    )
    (comp (ref "SICDIODE3")
      (value "C2M0280120D_C2M0280120D")
      (footprint "eagle-import:C2M0280120D_TO544P521X1594X2550-3P")
      (fields
        (field (name "MANUFACTURER_PART_NUMBER") "C2M0280120D")
        (field (name "RS_PART_NUMBER") "9158820P")
      )
      (libsource (lib "eagle-import") (part "C2M0280120D_C2M0280120D"))
    )
    (comp (ref "SJ4")
      (value "JUMPER_SJ")
      (footprint "eagle-import:JUMPER_SJ")
      (libsource (lib "eagle-import") (part "JUMPER_SJ"))
    )
    (comp (ref "SJ8")
      (value "JUMPER_SJ")
      (footprint "eagle-import:JUMPER_SJ")
      (libsource (lib "eagle-import") (part "JUMPER_SJ"))
    )
    (comp (ref "SJ9")
      (value "JUMPER_SJ")
      (footprint "eagle-import:JUMPER_SJ")
      (libsource (lib "eagle-import") (part "JUMPER_SJ"))
    )
    (comp (ref "SJ10")
      (value "JUMPER_SJ")
      (footprint "eagle-import:JUMPER_SJ")
      (libsource (lib "eagle-import") (part "JUMPER_SJ"))
    )
    (comp (ref "SJ11")
      (value "JUMPER_SJ")
      (footprint "eagle-import:JUMPER_SJ")
      (libsource (lib "eagle-import") (part "JUMPER_SJ"))
    )
    (comp (ref "SJ12")
      (value "JUMPER_SJ")
      (footprint "eagle-import:JUMPER_SJ")
      (libsource (lib "eagle-import") (part "JUMPER_SJ"))
    )
    (comp (ref "TP3")
      (value "TPTP15SQ")
      (footprint "eagle-import:TP15SQ")
      (libsource (lib "eagle-import") (part "TPTP15SQ"))
    )
    (comp (ref "TP7")
      (value "TPTP15SQ")
      (footprint "eagle-import:TP15SQ")
      (libsource (lib "eagle-import") (part "TPTP15SQ"))
    )
    (comp (ref "TP8")
      (value "TPTP15SQ")
      (footprint "eagle-import:TP15SQ")
      (libsource (lib "eagle-import") (part "TPTP15SQ"))
    )
    (comp (ref "TP9")
      (value "TPTP15SQ")
      (footprint "eagle-import:TP15SQ")
      (libsource (lib "eagle-import") (part "TPTP15SQ"))
    )
    (comp (ref "TP10")
      (value "TPTP15SQ")
      (footprint "eagle-import:TP15SQ")
      (libsource (lib "eagle-import") (part "TPTP15SQ"))
    )
    (comp (ref "U$1")
      (value "SO24E-IC_STGAP1AS")
      (footprint "eagle-import:SO24E-IC_SO24W")
      (libsource (lib "eagle-import") (part "SO24E-IC_STGAP1AS"))
    )
    (comp (ref "U$3")
      (value "SO24E-IC_STGAP1AS")
      (footprint "eagle-import:SO24E-IC_SO24W")
      (libsource (lib "eagle-import") (part "SO24E-IC_STGAP1AS"))
    )
    (comp (ref "U1")
      (value "SAMACSYS_LIB_MGJ2D052005SC")
      (footprint "eagle-import:SAMACSYS_LIB_MGJ2D_7-PIN-SIP")
      (fields (field (name "ARROW_PART_NUMBER") "MGJ2D052005SC") (field (name "RS_PART_NUMBER") "8163506P"))
      (libsource (lib "eagle-import") (part "SAMACSYS_LIB_MGJ2D052005SC"))
    )
    (comp (ref "U4")
      (value "SAMACSYS_LIB_MGJ2D052005SC")
      (footprint "eagle-import:SAMACSYS_LIB_MGJ2D_7-PIN-SIP")
      (fields (field (name "ARROW_PART_NUMBER") "MGJ2D052005SC") (field (name "RS_PART_NUMBER") "8163506P"))
      (libsource (lib "eagle-import") (part "SAMACSYS_LIB_MGJ2D052005SC"))
    )
    (comp (ref "X4")
      (value "234-502")
      (footprint "eagle-import:234-502")
      (libsource (lib "eagle-import") (part "234-502"))
    )
    (comp (ref "X5")
      (value "234-502")
      (footprint "eagle-import:234-502")
      (libsource (lib "eagle-import") (part "234-502"))
    )
    (comp (ref "X6")
      (value "234-502")
      (footprint "eagle-import:234-502")
      (libsource (lib "eagle-import") (part "234-502"))
    )
    (comp (ref "C1")
      (value "2.2uF")
      (footprint "eagle-import:SPARKFUN-CAPACITORS_1206")
      (libsource (lib "eagle-import") (part "SPARKFUN-CAPACITORS_2.2UF-1206-50V-10%"))
    )
    (comp (ref "C2")
      (value "2.2uF")
      (footprint "eagle-import:SPARKFUN-CAPACITORS_1206")
      (libsource (lib "eagle-import") (part "SPARKFUN-CAPACITORS_2.2UF-1206-50V-10%"))
    )
    (comp (ref "C3")
      (value "0.1uF")
      (footprint "eagle-import:SPARKFUN-CAPACITORS_0603")
      (libsource (lib "eagle-import") (part "SPARKFUN-CAPACITORS_0.1UF-0603-100V-10%"))
    )
    (comp (ref "C4")
      (value "10uF")
      (footprint "eagle-import:SPARKFUN-CAPACITORS_1210")
      (libsource (lib "eagle-import") (part "SPARKFUN-CAPACITORS_10UF-1210-50V-20%"))
    )
    (comp (ref "C5")
      (value "0.1uF")
      (footprint "eagle-import:SPARKFUN-CAPACITORS_0603")
      (libsource (lib "eagle-import") (part "SPARKFUN-CAPACITORS_0.1UF-0603-100V-10%"))
    )
    (comp (ref "C6")
      (value "10uF")
      (footprint "eagle-import:SPARKFUN-CAPACITORS_1210")
      (libsource (lib "eagle-import") (part "SPARKFUN-CAPACITORS_10UF-1210-50V-20%"))
    )
    (comp (ref "C7")
      (value "0.1uF")
      (footprint "eagle-import:SPARKFUN-CAPACITORS_0603")
      (libsource (lib "eagle-import") (part "SPARKFUN-CAPACITORS_0.1UF-0603-100V-10%"))
    )
    (comp (ref "C8")
      (value "100pF")
      (footprint "eagle-import:SPARKFUN-CAPACITORS_0603")
      (libsource (lib "eagle-import") (part "SPARKFUN-CAPACITORS_100PF-0603-50V-5%"))
    )
    (comp (ref "C9")
      (value "100pF")
      (footprint "eagle-import:SPARKFUN-CAPACITORS_0603")
      (libsource (lib "eagle-import") (part "SPARKFUN-CAPACITORS_100PF-0603-50V-5%"))
    )
    (comp (ref "C10")
      (value "0.1uF")
      (footprint "eagle-import:SPARKFUN-CAPACITORS_0603")
      (libsource (lib "eagle-import") (part "SPARKFUN-CAPACITORS_0.1UF-0603-100V-10%"))
    )
    (comp (ref "C11")
      (value "0.1uF")
      (footprint "eagle-import:SPARKFUN-CAPACITORS_0603")
      (libsource (lib "eagle-import") (part "SPARKFUN-CAPACITORS_0.1UF-0603-100V-10%"))
    )
    (comp (ref "C12")
      (value "1nF")
      (footprint "eagle-import:SPARKFUN-CAPACITORS_0603")
      (libsource (lib "eagle-import") (part "SPARKFUN-CAPACITORS_1.0NF/1000PF-0603-50V-10%"))
    )
    (comp (ref "C13")
      (value "100pF")
      (footprint "eagle-import:SPARKFUN-CAPACITORS_0603")
      (libsource (lib "eagle-import") (part "SPARKFUN-CAPACITORS_100PF-0603-50V-5%"))
    )
    (comp (ref "C14")
      (value "4.7uF")
      (footprint "eagle-import:SPARKFUN-CAPACITORS_0603")
      (libsource (lib "eagle-import") (part "SPARKFUN-CAPACITORS_4.7UF0603"))
    )
    (comp (ref "C15")
      (value "100pF")
      (footprint "eagle-import:SPARKFUN-CAPACITORS_0603")
      (libsource (lib "eagle-import") (part "SPARKFUN-CAPACITORS_100PF-0603-50V-5%"))
    )
    (comp (ref "C16")
      (value "0.1uF")
      (footprint "eagle-import:SPARKFUN-CAPACITORS_0603")
      (libsource (lib "eagle-import") (part "SPARKFUN-CAPACITORS_0.1UF-0603-100V-10%"))
    )
    (comp (ref "C17")
      (value "1.0uF")
      (footprint "eagle-import:SPARKFUN-CAPACITORS_0805")
      (libsource (lib "eagle-import") (part "SPARKFUN-CAPACITORS_1.0UF-0805-25V-10%"))
    )
    (comp (ref "C18")
      (value "1.0uF")
      (footprint "eagle-import:SPARKFUN-CAPACITORS_0805")
      (libsource (lib "eagle-import") (part "SPARKFUN-CAPACITORS_1.0UF-0805-25V-10%"))
    )
    (comp (ref "C19")
      (value "4.7uF")
      (footprint "eagle-import:SPARKFUN-CAPACITORS_0603")
      (libsource (lib "eagle-import") (part "SPARKFUN-CAPACITORS_4.7UF0603"))
    )
    (comp (ref "C20")
      (value "100pF")
      (footprint "eagle-import:SPARKFUN-CAPACITORS_0603")
      (libsource (lib "eagle-import") (part "SPARKFUN-CAPACITORS_100PF-0603-50V-5%"))
    )
    (comp (ref "C21")
      (value "47pF")
      (footprint "eagle-import:SPARKFUN-CAPACITORS_0603")
      (libsource (lib "eagle-import") (part "SPARKFUN-CAPACITORS_47PF-0603-50V-5%"))
    )
    (comp (ref "C22")
      (value "47pF")
      (footprint "eagle-import:SPARKFUN-CAPACITORS_0603")
      (libsource (lib "eagle-import") (part "SPARKFUN-CAPACITORS_47PF-0603-50V-5%"))
    )
    (comp (ref "C23")
      (value "47pF")
      (footprint "eagle-import:SPARKFUN-CAPACITORS_0603")
      (libsource (lib "eagle-import") (part "SPARKFUN-CAPACITORS_47PF-0603-50V-5%"))
    )
    (comp (ref "C24")
      (value "1nF")
      (footprint "eagle-import:SPARKFUN-CAPACITORS_0603")
      (libsource (lib "eagle-import") (part "SPARKFUN-CAPACITORS_1.0NF/1000PF-0603-50V-10%"))
    )
    (comp (ref "C25")
      (value "4.7uF")
      (footprint "eagle-import:SPARKFUN-CAPACITORS_0603")
      (libsource (lib "eagle-import") (part "SPARKFUN-CAPACITORS_4.7UF0603"))
    )
    (comp (ref "C26")
      (value "0.1uF")
      (footprint "eagle-import:SPARKFUN-CAPACITORS_0603")
      (libsource (lib "eagle-import") (part "SPARKFUN-CAPACITORS_0.1UF-0603-100V-10%"))
    )
    (comp (ref "C27")
      (value "0.1uF")
      (footprint "eagle-import:SPARKFUN-CAPACITORS_0603")
      (libsource (lib "eagle-import") (part "SPARKFUN-CAPACITORS_0.1UF-0603-100V-10%"))
    )
    (comp (ref "C28")
      (value "0.1uF")
      (footprint "eagle-import:SPARKFUN-CAPACITORS_0603")
      (libsource (lib "eagle-import") (part "SPARKFUN-CAPACITORS_0.1UF-0603-100V-10%"))
    )
    (comp (ref "C29")
      (value "0.1uF")
      (footprint "eagle-import:SPARKFUN-CAPACITORS_0603")
      (libsource (lib "eagle-import") (part "SPARKFUN-CAPACITORS_0.1UF-0603-100V-10%"))
    )
    (comp (ref "C30")
      (value "1.0uF")
      (footprint "eagle-import:SPARKFUN-CAPACITORS_0805")
      (libsource (lib "eagle-import") (part "SPARKFUN-CAPACITORS_1.0UF-0805-25V-10%"))
    )
    (comp (ref "C31")
      (value "1.0uF")
      (footprint "eagle-import:SPARKFUN-CAPACITORS_0805")
      (libsource (lib "eagle-import") (part "SPARKFUN-CAPACITORS_1.0UF-0805-25V-10%"))
    )
    (comp (ref "C32")
      (value "2.2uF")
      (footprint "eagle-import:SPARKFUN-CAPACITORS_1206")
      (fields (field (name "SPICEPREFIX") "C"))
      (libsource (lib "eagle-import") (part "SPARKFUN-CAPACITORS_2.2UF-1206-50V-10%"))
    )
    (comp (ref "C33")
      (value "2.2uF")
      (footprint "eagle-import:SPARKFUN-CAPACITORS_1206")
      (libsource (lib "eagle-import") (part "SPARKFUN-CAPACITORS_2.2UF-1206-50V-10%"))
    )
    (comp (ref "C34")
      (value "4.7uF")
      (footprint "eagle-import:SPARKFUN-CAPACITORS_0603")
      (libsource (lib "eagle-import") (part "SPARKFUN-CAPACITORS_4.7UF0603"))
    )
    (comp (ref "C35")
      (value "0.1uF")
      (footprint "eagle-import:SPARKFUN-CAPACITORS_0603")
      (libsource (lib "eagle-import") (part "SPARKFUN-CAPACITORS_0.1UF-0603-100V-10%"))
    )
    (comp (ref "C36")
      (value "0.1uF")
      (footprint "eagle-import:SPARKFUN-CAPACITORS_0603")
      (libsource (lib "eagle-import") (part "SPARKFUN-CAPACITORS_0.1UF-0603-100V-10%"))
    )
    (comp (ref "C37")
      (value "47pF")
      (footprint "eagle-import:SPARKFUN-CAPACITORS_0603")
      (libsource (lib "eagle-import") (part "SPARKFUN-CAPACITORS_47PF-0603-50V-5%"))
    )
    (comp (ref "C38")
      (value "47pF")
      (footprint "eagle-import:SPARKFUN-CAPACITORS_0603")
      (libsource (lib "eagle-import") (part "SPARKFUN-CAPACITORS_47PF-0603-50V-5%"))
    )
    (comp (ref "C39")
      (value "47pF")
      (footprint "eagle-import:SPARKFUN-CAPACITORS_0603")
      (libsource (lib "eagle-import") (part "SPARKFUN-CAPACITORS_47PF-0603-50V-5%"))
    )
    (comp (ref "C40")
      (value "100pF")
      (footprint "eagle-import:SPARKFUN-CAPACITORS_0603")
      (libsource (lib "eagle-import") (part "SPARKFUN-CAPACITORS_100PF-0603-50V-5%"))
    )
    (comp (ref "C41")
      (value "100pF")
      (footprint "eagle-import:SPARKFUN-CAPACITORS_0603")
      (libsource (lib "eagle-import") (part "SPARKFUN-CAPACITORS_100PF-0603-50V-5%"))
    )
    (comp (ref "C42")
      (value "100pF")
      (footprint "eagle-import:SPARKFUN-CAPACITORS_0603")
      (libsource (lib "eagle-import") (part "SPARKFUN-CAPACITORS_100PF-0603-50V-5%"))
    )
    (comp (ref "C43")
      (value "10uF")
      (footprint "eagle-import:SPARKFUN-CAPACITORS_1210")
      (libsource (lib "eagle-import") (part "SPARKFUN-CAPACITORS_10UF-1210-50V-20%"))
    )
    (comp (ref "C45")
      (value "100pF")
      (footprint "eagle-import:SPARKFUN-CAPACITORS_0603")
      (libsource (lib "eagle-import") (part "SPARKFUN-CAPACITORS_100PF-0603-50V-5%"))
    )
    (comp (ref "C46")
      (value "100pF")
      (footprint "eagle-import:SPARKFUN-CAPACITORS_0603")
      (libsource (lib "eagle-import") (part "SPARKFUN-CAPACITORS_100PF-0603-50V-5%"))
    )
    (comp (ref "C47")
      (value "C-EU225-062X268")
      (footprint "eagle-import:C225-062X268")
      (libsource (lib "eagle-import") (part "C-EU225-062X268"))
    )
    (comp (ref "C48")
      (value "C-EU225-062X268")
      (footprint "eagle-import:C225-062X268")
      (libsource (lib "eagle-import") (part "C-EU225-062X268"))
    )
    (comp (ref "D1")
      (value "BAT54SFILM_BAT54SFILM")
      (footprint "eagle-import:BAT54SFILM_SOT105P242X150-3N")
      (fields
        (field (name "MANUFACTURER_PART_NUMBER") "BAT54SFILM")
        (field (name "RS_PART_NUMBER") "7146863P")
      )
      (libsource (lib "eagle-import") (part "BAT54SFILM_BAT54SFILM"))
    )
    (comp (ref "D2")
      (value "STTH112A_STTH112A")
      (footprint "eagle-import:STTH112A_DIOM5126X265N")
      (fields (field (name "MANUFACTURER_PART_NUMBER") "STTH112A") (field (name "RS_PART_NUMBER") "0249319"))
      (libsource (lib "eagle-import") (part "STTH112A_STTH112A"))
    )
    (comp (ref "D3")
      (value "STPS2H100A_STPS2H100A")
      (footprint "eagle-import:STPS2H100A_DIOM5126X265N")
      (fields
        (field (name "MANUFACTURER_PART_NUMBER") "STPS2H100A")
        (field (name "RS_PART_NUMBER") "0249612P")
      )
      (libsource (lib "eagle-import") (part "STPS2H100A_STPS2H100A"))
    )
    (comp (ref "D4")
      (value "BAT20JFILM_BAT20JFILM")
      (footprint "eagle-import:BAT20JFILM_SOD2512X113N")
      (fields
        (field (name "MANUFACTURER_PART_NUMBER") "BAT20JFILM")
        (field (name "RS_PART_NUMBER") "1657545")
      )
      (libsource (lib "eagle-import") (part "BAT20JFILM_BAT20JFILM"))
    )
    (comp (ref "D5")
      (value "STTH112A_STTH112A")
      (footprint "eagle-import:STTH112A_DIOM5126X265N")
      (fields (field (name "MANUFACTURER_PART_NUMBER") "STTH112A") (field (name "RS_PART_NUMBER") "0249319"))
      (libsource (lib "eagle-import") (part "STTH112A_STTH112A"))
    )
    (comp (ref "D6")
      (value "BAT20JFILM_BAT20JFILM")
      (footprint "eagle-import:BAT20JFILM_SOD2512X113N")
      (fields
        (field (name "MANUFACTURER_PART_NUMBER") "BAT20JFILM")
        (field (name "RS_PART_NUMBER") "1657545")
      )
      (libsource (lib "eagle-import") (part "BAT20JFILM_BAT20JFILM"))
    )
    (comp (ref "D7")
      (value "BAT54SFILM_BAT54SFILM")
      (footprint "eagle-import:BAT54SFILM_SOT105P242X150-3N")
      (fields
        (field (name "MANUFACTURER_PART_NUMBER") "BAT54SFILM")
        (field (name "RS_PART_NUMBER") "7146863P")
        (field (name "SPICEPREFIX") "J")
      )
      (libsource (lib "eagle-import") (part "BAT54SFILM_BAT54SFILM"))
    )
    (comp (ref "D8")
      (value "STPS2H100A_STPS2H100A")
      (footprint "eagle-import:STPS2H100A_DIOM5126X265N")
      (fields
        (field (name "MANUFACTURER_PART_NUMBER") "STPS2H100A")
        (field (name "RS_PART_NUMBER") "0249612P")
        (field (name "SPICEPREFIX") "D")
      )
      (libsource (lib "eagle-import") (part "STPS2H100A_STPS2H100A"))
    )
    (comp (ref "D9-D.N.M")
      (value "STPS2H100A_STPS2H100A")
      (footprint "eagle-import:STPS2H100A_DIOM5126X265N")
      (fields
        (field (name "MANUFACTURER_PART_NUMBER") "STPS2H100A")
        (field (name "RS_PART_NUMBER") "0249612P")
      )
      (libsource (lib "eagle-import") (part "STPS2H100A_STPS2H100A"))
    )
    (comp (ref "D9-D.N.M.2")
      (value "STPS2H100A_STPS2H100A")
      (footprint "eagle-import:STPS2H100A_DIOM5126X265N")
      (fields
        (field (name "MANUFACTURER_PART_NUMBER") "STPS2H100A")
        (field (name "RS_PART_NUMBER") "0249612P")
        (field (name "SPICEPREFIX") "D")
      )
      (libsource (lib "eagle-import") (part "STPS2H100A_STPS2H100A"))
    )
    (comp (ref "DL1")
      (value "RED")
      (footprint "eagle-import:SPARKFUN-LED_LED-1206")
      (libsource (lib "eagle-import") (part "SPARKFUN-LED_LED-RED1206"))
    )
    (comp (ref "DL2")
      (value "RED")
      (footprint "eagle-import:SPARKFUN-LED_LED-1206")
      (libsource (lib "eagle-import") (part "SPARKFUN-LED_LED-RED1206"))
    )
    (comp (ref "DL3")
      (value "RED")
      (footprint "eagle-import:SPARKFUN-LED_LED-1206")
      (libsource (lib "eagle-import") (part "SPARKFUN-LED_LED-RED1206"))
    )
    (comp (ref "DL4")
      (value "RED")
      (footprint "eagle-import:SPARKFUN-LED_LED-1206")
      (libsource (lib "eagle-import") (part "SPARKFUN-LED_LED-RED1206"))
    )
    (comp (ref "IC1")
      (value "NATIONAL-SEMICONDUCTOR_LM2936MP-3.0")
      (footprint "eagle-import:NATIONAL-SEMICONDUCTOR_SOT223")
      (fields (field (name "MF") "NATIONAL SEMICONDUCTOR") (field (name "MPN") "LM2936MP-3.0/NOPB"))
      (libsource (lib "eagle-import") (part "NATIONAL-SEMICONDUCTOR_LM2936MP?-3.0"))
    )
    (comp (ref "J1")
      (value "SPARKFUN-CONNECTORS_CONN_12LONGPADS")
      (footprint "eagle-import:SPARKFUN-CONNECTORS_1X12_LONGPADS")
      (libsource (lib "eagle-import") (part "SPARKFUN-CONNECTORS_CONN_12LONGPADS"))
    )
    (comp (ref "J2")
      (value "SPARKFUN-CONNECTORS_CONN_03LONGPADS")
      (footprint "eagle-import:SPARKFUN-CONNECTORS_1X03_LONGPADS")
      (libsource (lib "eagle-import") (part "SPARKFUN-CONNECTORS_CONN_03LONGPADS"))
    )
    (comp (ref "J3")
      (value "SPARKFUN-CONNECTORS_CONN_04LONGPADS")
      (footprint "eagle-import:SPARKFUN-CONNECTORS_1X04_LONGPADS")
      (libsource (lib "eagle-import") (part "SPARKFUN-CONNECTORS_CONN_04LONGPADS"))
    )
    (comp (ref "J4")
      (value "SPARKFUN-CONNECTORS_CONN_04LONGPADS")
      (footprint "eagle-import:SPARKFUN-CONNECTORS_1X04_LONGPADS")
      (libsource (lib "eagle-import") (part "SPARKFUN-CONNECTORS_CONN_04LONGPADS"))
    )
    (comp (ref "MICROCONTROLLER_POWER1")
      (value "SPARKFUN-CONNECTORS_CONN_025MM")
      (footprint "eagle-import:SPARKFUN-CONNECTORS_SCREWTERMINAL-5MM-2")
      (libsource (lib "eagle-import") (part "SPARKFUN-CONNECTORS_CONN_025MM"))
    )
    (comp (ref "Q1")
      (value "C2M0280120D_C2M0280120D")
      (footprint "eagle-import:C2M0280120D_TO544P521X1594X2550-3P")
      (fields
        (field (name "MANUFACTURER_PART_NUMBER") "C2M0280120D")
        (field (name "RS_PART_NUMBER") "9158820P")
      )
      (libsource (lib "eagle-import") (part "C2M0280120D_C2M0280120D"))
    )
    (comp (ref "Q2")
      (value "C2M0280120D_C2M0280120D")
      (footprint "eagle-import:C2M0280120D_TO544P521X1594X2550-3P")
      (fields
        (field (name "MANUFACTURER_PART_NUMBER") "C2M0280120D")
        (field (name "RS_PART_NUMBER") "9158820P")
      )
      (libsource (lib "eagle-import") (part "C2M0280120D_C2M0280120D"))
    )
    (comp (ref "R1")
      (value "1k")
      (footprint "eagle-import:SPARKFUN-RESISTORS_0603")
      (libsource (lib "eagle-import") (part "SPARKFUN-RESISTORS_1KOHM-0603-1/10W-1%"))
    )
    (comp (ref "R1-D.N.M.2")
      (value "0")
      (footprint "eagle-import:SPARKFUN-RESISTORS_0603")
      (libsource (lib "eagle-import") (part "SPARKFUN-RESISTORS_0OHM-0603-1/10W-5%"))
    )
    (comp (ref "R2")
      (value "SPARKFUN-RESISTORS_RESISTOR0805")
      (footprint "eagle-import:SPARKFUN-RESISTORS_0805")
      (libsource (lib "eagle-import") (part "SPARKFUN-RESISTORS_RESISTOR0805"))
    )
    (comp (ref "R3")
      (value "SPARKFUN-RESISTORS_RESISTOR1206")
      (footprint "eagle-import:SPARKFUN-RESISTORS_1206")
      (libsource (lib "eagle-import") (part "SPARKFUN-RESISTORS_RESISTOR1206"))
    )
    (comp (ref "R4")
      (value "SPARKFUN-RESISTORS_RESISTOR1206")
      (footprint "eagle-import:SPARKFUN-RESISTORS_1206")
      (libsource (lib "eagle-import") (part "SPARKFUN-RESISTORS_RESISTOR1206"))
    )
    (comp (ref "R5")
      (value "SPARKFUN-RESISTORS_RESISTOR1206")
      (footprint "eagle-import:SPARKFUN-RESISTORS_1206")
      (libsource (lib "eagle-import") (part "SPARKFUN-RESISTORS_RESISTOR1206"))
    )
    (comp (ref "R6")
      (value "SPARKFUN-RESISTORS_RESISTOR1206")
      (footprint "eagle-import:SPARKFUN-RESISTORS_1206")
      (libsource (lib "eagle-import") (part "SPARKFUN-RESISTORS_RESISTOR1206"))
    )
    (comp (ref "R7")
      (value "47k")
      (footprint "eagle-import:SPARKFUN-RESISTORS_0603")
      (libsource (lib "eagle-import") (part "SPARKFUN-RESISTORS_47KOHM-0603-1/10W-1%"))
    )
    (comp (ref "R8")
      (value "1k")
      (footprint "eagle-import:SPARKFUN-RESISTORS_0603")
      (libsource (lib "eagle-import") (part "SPARKFUN-RESISTORS_1KOHM-0603-1/10W-1%"))
    )
    (comp (ref "R9")
      (value "0")
      (footprint "eagle-import:SPARKFUN-RESISTORS_0603")
      (libsource (lib "eagle-import") (part "SPARKFUN-RESISTORS_0OHM-0603-1/10W-5%"))
    )
    (comp (ref "R10")
      (value "1k")
      (footprint "eagle-import:SPARKFUN-RESISTORS_0603")
      (libsource (lib "eagle-import") (part "SPARKFUN-RESISTORS_1KOHM-0603-1/10W-1%"))
    )
    (comp (ref "R11")
      (value "SPARKFUN-RESISTORS_RESISTOR0603")
      (footprint "eagle-import:SPARKFUN-RESISTORS_0603")
      (libsource (lib "eagle-import") (part "SPARKFUN-RESISTORS_RESISTOR0603"))
    )
    (comp (ref "R12")
      (value "100")
      (footprint "eagle-import:SPARKFUN-RESISTORS_0603")
      (libsource (lib "eagle-import") (part "SPARKFUN-RESISTORS_100OHM-0603-1/4W-5%"))
    )
    (comp (ref "R13")
      (value "100")
      (footprint "eagle-import:SPARKFUN-RESISTORS_0603")
      (libsource (lib "eagle-import") (part "SPARKFUN-RESISTORS_100OHM-0603-1/4W-5%"))
    )
    (comp (ref "R14")
      (value "SPARKFUN-RESISTORS_RESISTOR0603")
      (footprint "eagle-import:SPARKFUN-RESISTORS_0603")
      (libsource (lib "eagle-import") (part "SPARKFUN-RESISTORS_RESISTOR0603"))
    )
    (comp (ref "R15-D.N.M")
      (value "0")
      (footprint "eagle-import:SPARKFUN-RESISTORS_0603")
      (libsource (lib "eagle-import") (part "SPARKFUN-RESISTORS_0OHM-0603-1/10W-5%"))
    )
    (comp (ref "R16")
      (value "100")
      (footprint "eagle-import:SPARKFUN-RESISTORS_0603")
      (libsource (lib "eagle-import") (part "SPARKFUN-RESISTORS_100OHM-0603-1/4W-5%"))
    )
    (comp (ref "R20")
      (value "SPARKFUN-RESISTORS_RESISTOR1206")
      (footprint "eagle-import:SPARKFUN-RESISTORS_1206")
      (libsource (lib "eagle-import") (part "SPARKFUN-RESISTORS_RESISTOR1206"))
    )
    (comp (ref "R21")
      (value "SPARKFUN-RESISTORS_RESISTOR1206")
      (footprint "eagle-import:SPARKFUN-RESISTORS_1206")
      (libsource (lib "eagle-import") (part "SPARKFUN-RESISTORS_RESISTOR1206"))
    )
    (comp (ref "R22")
      (value "1k")
      (footprint "eagle-import:SPARKFUN-RESISTORS_0603")
      (libsource (lib "eagle-import") (part "SPARKFUN-RESISTORS_1KOHM-0603-1/10W-1%"))
    )
    (comp (ref "R23")
      (value "47k")
      (footprint "eagle-import:SPARKFUN-RESISTORS_0603")
      (libsource (lib "eagle-import") (part "SPARKFUN-RESISTORS_47KOHM-0603-1/10W-1%"))
    )
    (comp (ref "R30")
      (value "100")
      (footprint "eagle-import:SPARKFUN-RESISTORS_0603")
      (libsource (lib "eagle-import") (part "SPARKFUN-RESISTORS_100OHM-0603-1/4W-5%"))
    )
    (comp (ref "R31")
      (value "SPARKFUN-RESISTORS_RESISTOR0603")
      (footprint "eagle-import:SPARKFUN-RESISTORS_0603")
      (libsource (lib "eagle-import") (part "SPARKFUN-RESISTORS_RESISTOR0603"))
    )
    (comp (ref "R32")
      (value "SPARKFUN-RESISTORS_RESISTOR0603")
      (footprint "eagle-import:SPARKFUN-RESISTORS_0603")
      (libsource (lib "eagle-import") (part "SPARKFUN-RESISTORS_RESISTOR0603"))
    )
    (comp (ref "R33")
      (value "100")
      (footprint "eagle-import:SPARKFUN-RESISTORS_0603")
      (libsource (lib "eagle-import") (part "SPARKFUN-RESISTORS_100OHM-0603-1/4W-5%"))
    )
    (comp (ref "R34")
      (value "0")
      (footprint "eagle-import:SPARKFUN-RESISTORS_0603")
      (libsource (lib "eagle-import") (part "SPARKFUN-RESISTORS_0OHM-0603-1/10W-5%"))
    )
    (comp (ref "R35")
      (value "SPARKFUN-RESISTORS_RESISTOR0805")
      (footprint "eagle-import:SPARKFUN-RESISTORS_0805")
      (libsource (lib "eagle-import") (part "SPARKFUN-RESISTORS_RESISTOR0805"))
    )
    (comp (ref "R36")
      (value "SPARKFUN-RESISTORS_RESISTOR1206")
      (footprint "eagle-import:SPARKFUN-RESISTORS_1206")
      (libsource (lib "eagle-import") (part "SPARKFUN-RESISTORS_RESISTOR1206"))
    )
    (comp (ref "R37")
      (value "SPARKFUN-RESISTORS_RESISTOR1206")
      (footprint "eagle-import:SPARKFUN-RESISTORS_1206")
      (libsource (lib "eagle-import") (part "SPARKFUN-RESISTORS_RESISTOR1206"))
    )
    (comp (ref "R38")
      (value "SPARKFUN-RESISTORS_RESISTOR1206")
      (footprint "eagle-import:SPARKFUN-RESISTORS_1206")
      (libsource (lib "eagle-import") (part "SPARKFUN-RESISTORS_RESISTOR1206"))
    )
    (comp (ref "R39")
      (value "SPARKFUN-RESISTORS_RESISTOR1206")
      (footprint "eagle-import:SPARKFUN-RESISTORS_1206")
      (libsource (lib "eagle-import") (part "SPARKFUN-RESISTORS_RESISTOR1206"))
    )
    (comp (ref "SICDIODE")
      (value "C2M0280120D_C2M0280120D")
      (footprint "eagle-import:C2M0280120D_TO544P521X1594X2550-3P")
      (fields
        (field (name "MANUFACTURER_PART_NUMBER") "C2M0280120D")
        (field (name "RS_PART_NUMBER") "9158820P")
      )
      (libsource (lib "eagle-import") (part "C2M0280120D_C2M0280120D"))
    )
    (comp (ref "SICDIODE2")
      (value "C2M0280120D_C2M0280120D")
      (footprint "eagle-import:C2M0280120D_TO544P521X1594X2550-3P")
      (fields
        (field (name "MANUFACTURER_PART_NUMBER") "C2M0280120D")
        (field (name "RS_PART_NUMBER") "9158820P")
      )
      (libsource (lib "eagle-import") (part "C2M0280120D_C2M0280120D"))
    )
    (comp (ref "SJ1")
      (value "JUMPER_SJ")
      (footprint "eagle-import:JUMPER_SJ")
      (libsource (lib "eagle-import") (part "JUMPER_SJ"))
    )
    (comp (ref "SJ2")
      (value "JUMPER_SJ")
      (footprint "eagle-import:JUMPER_SJ")
      (libsource (lib "eagle-import") (part "JUMPER_SJ"))
    )
    (comp (ref "SJ3")
      (value "JUMPER_SJ")
      (footprint "eagle-import:JUMPER_SJ")
      (libsource (lib "eagle-import") (part "JUMPER_SJ"))
    )
    (comp (ref "SJ5")
      (value "JUMPER_SJ")
      (footprint "eagle-import:JUMPER_SJ")
      (libsource (lib "eagle-import") (part "JUMPER_SJ"))
    )
    (comp (ref "SJ6")
      (value "JUMPER_SJ")
      (footprint "eagle-import:JUMPER_SJ")
      (libsource (lib "eagle-import") (part "JUMPER_SJ"))
    )
    (comp (ref "SJ7")
      (value "JUMPER_SJ")
      (footprint "eagle-import:JUMPER_SJ")
      (libsource (lib "eagle-import") (part "JUMPER_SJ"))
    )
    (comp (ref "TP1")
      (value "TPTP15SQ")
      (footprint "eagle-import:TP15SQ")
      (libsource (lib "eagle-import") (part "TPTP15SQ"))
    )
    (comp (ref "TP2")
      (value "TPTP15SQ")
      (footprint "eagle-import:TP15SQ")
      (libsource (lib "eagle-import") (part "TPTP15SQ"))
    )
    (comp (ref "TP4")
      (value "TPTP15SQ")
      (footprint "eagle-import:TP15SQ")
      (libsource (lib "eagle-import") (part "TPTP15SQ"))
    )
    (comp (ref "TP5")
      (value "TPTP15SQ")
      (footprint "eagle-import:TP15SQ")
      (libsource (lib "eagle-import") (part "TPTP15SQ"))
    )
    (comp (ref "TP6")
      (value "TPTP15SQ")
      (footprint "eagle-import:TP15SQ")
      (libsource (lib "eagle-import") (part "TPTP15SQ"))
    )
    (comp (ref "U$2")
      (value "SO24E-IC_STGAP1AS")
      (footprint "eagle-import:SO24E-IC_SO24W")
      (libsource (lib "eagle-import") (part "SO24E-IC_STGAP1AS"))
    )
    (comp (ref "U$5")
      (value "SO24E-IC_STGAP1AS")
      (footprint "eagle-import:SO24E-IC_SO24W")
      (libsource (lib "eagle-import") (part "SO24E-IC_STGAP1AS"))
    )
    (comp (ref "U2")
      (value "SAMACSYS_LIB_MGJ2D052005SC")
      (footprint "eagle-import:SAMACSYS_LIB_MGJ2D_7-PIN-SIP")
      (fields (field (name "ARROW_PART_NUMBER") "MGJ2D052005SC") (field (name "RS_PART_NUMBER") "8163506P"))
      (libsource (lib "eagle-import") (part "SAMACSYS_LIB_MGJ2D052005SC"))
    )
    (comp (ref "U3")
      (value "SAMACSYS_LIB_MGJ2D052005SC")
      (footprint "eagle-import:SAMACSYS_LIB_MGJ2D_7-PIN-SIP")
      (fields (field (name "ARROW_PART_NUMBER") "MGJ2D052005SC") (field (name "RS_PART_NUMBER") "8163506P"))
      (libsource (lib "eagle-import") (part "SAMACSYS_LIB_MGJ2D052005SC"))
    )
    (comp (ref "X1")
      (value "234-502")
      (footprint "eagle-import:234-502")
      (libsource (lib "eagle-import") (part "234-502"))
    )
    (comp (ref "X2")
      (value "234-502")
      (footprint "eagle-import:234-502")
      (libsource (lib "eagle-import") (part "234-502"))
    )
    (comp (ref "X3")
      (value "234-502")
      (footprint "eagle-import:234-502")
      (libsource (lib "eagle-import") (part "234-502"))
    )
  )
  (nets
    (net (code "1") (name "CK") (class "Default")
      (node (ref "C22") (pin "1") (pinfunction "1_1") (pintype "passive"))
      (node (ref "C38") (pin "1") (pinfunction "1_1") (pintype "passive"))
      (node (ref "J2") (pin "3") (pinfunction "3_3") (pintype "passive"))
      (node (ref "J3") (pin "3") (pinfunction "3_3") (pintype "passive"))
      (node (ref "J4") (pin "3") (pinfunction "3_3") (pintype "passive"))
      (node (ref "U$2") (pin "5") (pinfunction "CK_5") (pintype "input"))
      (node (ref "U$5") (pin "5") (pinfunction "CK_5") (pintype "input"))
    )
    (net (code "2") (name "CK_2") (class "Default")
      (node (ref "C63") (pin "1") (pinfunction "1_1") (pintype "passive"))
      (node (ref "C85") (pin "1") (pinfunction "1_1") (pintype "passive"))
      (node (ref "J6") (pin "3") (pinfunction "3_3") (pintype "passive"))
      (node (ref "J7") (pin "3") (pinfunction "3_3") (pintype "passive"))
      (node (ref "J8") (pin "3") (pinfunction "3_3") (pintype "passive"))
      (node (ref "U$1") (pin "5") (pinfunction "CK_5") (pintype "input"))
      (node (ref "U$3") (pin "5") (pinfunction "CK_5") (pintype "input"))
    )
    (net (code "3") (name "CS") (class "Default")
      (node (ref "C21") (pin "1") (pinfunction "1_1") (pintype "passive"))
      (node (ref "C37") (pin "1") (pinfunction "1_1") (pintype "passive"))
      (node (ref "J1") (pin "1") (pinfunction "1_1") (pintype "passive"))
      (node (ref "J3") (pin "2") (pinfunction "2_2") (pintype "passive"))
      (node (ref "J4") (pin "2") (pinfunction "2_2") (pintype "passive"))
      (node (ref "U$2") (pin "4") (pinfunction "/CS_4") (pintype "input"))
      (node (ref "U$5") (pin "4") (pinfunction "/CS_4") (pintype "input"))
    )
    (net (code "4") (name "CS_2") (class "Default")
      (node (ref "C62") (pin "1") (pinfunction "1_1") (pintype "passive"))
      (node (ref "C84") (pin "1") (pinfunction "1_1") (pintype "passive"))
      (node (ref "J5") (pin "1") (pinfunction "1_1") (pintype "passive"))
      (node (ref "J7") (pin "2") (pinfunction "2_2") (pintype "passive"))
      (node (ref "J8") (pin "2") (pinfunction "2_2") (pintype "passive"))
      (node (ref "U$1") (pin "4") (pinfunction "/CS_4") (pintype "input"))
      (node (ref "U$3") (pin "4") (pinfunction "/CS_4") (pintype "input"))
    )
    (net (code "5") (name "DESAT") (class "Default")
      (node (ref "C8") (pin "1") (pinfunction "1_1") (pintype "passive"))
      (node (ref "R10") (pin "1") (pinfunction "1_1") (pintype "passive"))
      (node (ref "U$5") (pin "18") (pinfunction "DESAT_18") (pintype "power_in"))
    )
    (net (code "6") (name "DESAT2") (class "Default")
      (node (ref "C20") (pin "1") (pinfunction "1_1") (pintype "passive"))
      (node (ref "R22") (pin "1") (pinfunction "1_1") (pintype "passive"))
      (node (ref "U$2") (pin "18") (pinfunction "DESAT_18") (pintype "power_in"))
    )
    (net (code "7") (name "DESAT2_2") (class "Default")
      (node (ref "C70") (pin "1") (pinfunction "1_1") (pintype "passive"))
      (node (ref "R45") (pin "1") (pinfunction "1_1") (pintype "passive"))
      (node (ref "U$1") (pin "18") (pinfunction "DESAT_18") (pintype "power_in"))
    )
    (net (code "8") (name "DESAT_2") (class "Default")
      (node (ref "C44") (pin "1") (pinfunction "1_1") (pintype "passive"))
      (node (ref "R17") (pin "1") (pinfunction "1_1") (pintype "passive"))
      (node (ref "U$3") (pin "18") (pinfunction "DESAT_18") (pintype "power_in"))
    )
    (net (code "9") (name "GND") (class "Default")
      (node (ref "C13") (pin "2") (pinfunction "2_2") (pintype "passive"))
      (node (ref "C15") (pin "2") (pinfunction "2_2") (pintype "passive"))
      (node (ref "C19") (pin "2") (pinfunction "2_2") (pintype "passive"))
      (node (ref "C21") (pin "2") (pinfunction "2_2") (pintype "passive"))
      (node (ref "C22") (pin "2") (pinfunction "2_2") (pintype "passive"))
      (node (ref "C23") (pin "2") (pinfunction "2_2") (pintype "passive"))
      (node (ref "C34") (pin "2") (pinfunction "2_2") (pintype "passive"))
      (node (ref "C35") (pin "2") (pinfunction "2_2") (pintype "passive"))
      (node (ref "C36") (pin "2") (pinfunction "2_2") (pintype "passive"))
      (node (ref "C37") (pin "2") (pinfunction "2_2") (pintype "passive"))
      (node (ref "C38") (pin "2") (pinfunction "2_2") (pintype "passive"))
      (node (ref "C39") (pin "2") (pinfunction "2_2") (pintype "passive"))
      (node (ref "C4") (pin "2") (pinfunction "2_2") (pintype "passive"))
      (node (ref "C40") (pin "2") (pinfunction "2_2") (pintype "passive"))
      (node (ref "C41") (pin "2") (pinfunction "2_2") (pintype "passive"))
      (node (ref "C42") (pin "2") (pinfunction "2_2") (pintype "passive"))
      (node (ref "C43") (pin "2") (pinfunction "2_2") (pintype "passive"))
      (node (ref "C5") (pin "2") (pinfunction "2_2") (pintype "passive"))
      (node (ref "C59") (pin "2") (pinfunction "2_2") (pintype "passive"))
      (node (ref "C6") (pin "2") (pinfunction "2_2") (pintype "passive"))
      (node (ref "C60") (pin "2") (pinfunction "2_2") (pintype "passive"))
      (node (ref "C61") (pin "2") (pinfunction "2_2") (pintype "passive"))
      (node (ref "C62") (pin "2") (pinfunction "2_2") (pintype "passive"))
      (node (ref "C63") (pin "2") (pinfunction "2_2") (pintype "passive"))
      (node (ref "C64") (pin "2") (pinfunction "2_2") (pintype "passive"))
      (node (ref "C65") (pin "2") (pinfunction "2_2") (pintype "passive"))
      (node (ref "C66") (pin "2") (pinfunction "2_2") (pintype "passive"))
      (node (ref "C67") (pin "2") (pinfunction "2_2") (pintype "passive"))
      (node (ref "C7") (pin "2") (pinfunction "2_2") (pintype "passive"))
      (node (ref "C81") (pin "2") (pinfunction "2_2") (pintype "passive"))
      (node (ref "C82") (pin "2") (pinfunction "2_2") (pintype "passive"))
      (node (ref "C83") (pin "2") (pinfunction "2_2") (pintype "passive"))
      (node (ref "C84") (pin "2") (pinfunction "2_2") (pintype "passive"))
      (node (ref "C85") (pin "2") (pinfunction "2_2") (pintype "passive"))
      (node (ref "C86") (pin "2") (pinfunction "2_2") (pintype "passive"))
      (node (ref "C87") (pin "2") (pinfunction "2_2") (pintype "passive"))
      (node (ref "C88") (pin "2") (pinfunction "2_2") (pintype "passive"))
      (node (ref "C89") (pin "2") (pinfunction "2_2") (pintype "passive"))
      (node (ref "C9") (pin "2") (pinfunction "2_2") (pintype "passive"))
      (node (ref "IC1") (pin "2") (pinfunction "GND_2") (pintype "passive"))
      (node (ref "IC1") (pin "4") (pinfunction "GND_4") (pintype "passive"))
      (node (ref "IC3") (pin "1") (pinfunction "GND_1_1") (pintype "bidirectional"))
      (node (ref "J1") (pin "11") (pinfunction "11_11") (pintype "passive"))
      (node (ref "J5") (pin "11") (pinfunction "11_11") (pintype "passive"))
      (node (ref "MICROCONTROLLER_POWER1") (pin "1") (pinfunction "1_1") (pintype "passive"))
      (node (ref "U$1") (pin "1") (pinfunction "GND_SIG_1") (pintype "power_in"))
      (node (ref "U$1") (pin "12") (pinfunction "GND_SIG_12") (pintype "power_in"))
      (node (ref "U$2") (pin "1") (pinfunction "GND_SIG_1") (pintype "power_in"))
      (node (ref "U$2") (pin "12") (pinfunction "GND_SIG_12") (pintype "power_in"))
      (node (ref "U$3") (pin "1") (pinfunction "GND_SIG_1") (pintype "power_in"))
      (node (ref "U$3") (pin "12") (pinfunction "GND_SIG_12") (pintype "power_in"))
      (node (ref "U$5") (pin "1") (pinfunction "GND_SIG_1") (pintype "power_in"))
      (node (ref "U$5") (pin "12") (pinfunction "GND_SIG_12") (pintype "power_in"))
      (node (ref "U1") (pin "2") (pinfunction "-VIN_2") (pintype "bidirectional"))
      (node (ref "U2") (pin "2") (pinfunction "-VIN_2") (pintype "bidirectional"))
      (node (ref "U3") (pin "2") (pinfunction "-VIN_2") (pintype "bidirectional"))
      (node (ref "U4") (pin "2") (pinfunction "-VIN_2") (pintype "bidirectional"))
    )
    (net (code "10") (name "GND_SIG") (class "Default")
      (node (ref "C1") (pin "2") (pinfunction "2_2") (pintype "passive"))
      (node (ref "C10") (pin "2") (pinfunction "2_2") (pintype "passive"))
      (node (ref "C11") (pin "2") (pinfunction "2_2") (pintype "passive"))
      (node (ref "C12") (pin "2") (pinfunction "2_2") (pintype "passive"))
      (node (ref "C14") (pin "2") (pinfunction "2_2") (pintype "passive"))
      (node (ref "C16") (pin "2") (pinfunction "2_2") (pintype "passive"))
      (node (ref "C17") (pin "2") (pinfunction "2_2") (pintype "passive"))
      (node (ref "C18") (pin "2") (pinfunction "2_2") (pintype "passive"))
      (node (ref "C2") (pin "2") (pinfunction "2_2") (pintype "passive"))
      (node (ref "C3") (pin "2") (pinfunction "2_2") (pintype "passive"))
      (node (ref "C45") (pin "2") (pinfunction "2_2") (pintype "passive"))
      (node (ref "C8") (pin "2") (pinfunction "2_2") (pintype "passive"))
      (node (ref "D2") (pin "1") (pinfunction "K_1") (pintype "bidirectional"))
      (node (ref "D9-D.N.M.2") (pin "1") (pinfunction "K_1") (pintype "bidirectional"))
      (node (ref "Q1") (pin "3") (pinfunction "S_3") (pintype "power_in"))
      (node (ref "Q2") (pin "2") (pinfunction "D_2") (pintype "power_in"))
      (node (ref "R1") (pin "2") (pinfunction "2_2") (pintype "passive"))
      (node (ref "R21") (pin "2") (pinfunction "2_2") (pintype "passive"))
      (node (ref "SICDIODE") (pin "1") (pinfunction "G_1") (pintype "input"))
      (node (ref "SICDIODE") (pin "3") (pinfunction "S_3") (pintype "power_in"))
      (node (ref "SICDIODE2") (pin "2") (pinfunction "D_2") (pintype "power_in"))
      (node (ref "U$5") (pin "13") (pinfunction "GNDISO_13") (pintype "power_in"))
      (node (ref "U2") (pin "6") (pinfunction "0V_6") (pintype "bidirectional"))
      (node (ref "X2") (pin "A1") (pinfunction "-1_A1") (pintype "passive"))
      (node (ref "X2") (pin "A2") (pinfunction "-2_A2") (pintype "passive"))
    )
    (net (code "11") (name "GND_SIG2") (class "Default")
      (node (ref "C20") (pin "2") (pinfunction "2_2") (pintype "passive"))
      (node (ref "C24") (pin "2") (pinfunction "2_2") (pintype "passive"))
      (node (ref "C25") (pin "2") (pinfunction "2_2") (pintype "passive"))
      (node (ref "C26") (pin "2") (pinfunction "2_2") (pintype "passive"))
      (node (ref "C27") (pin "2") (pinfunction "2_2") (pintype "passive"))
      (node (ref "C28") (pin "2") (pinfunction "2_2") (pintype "passive"))
      (node (ref "C29") (pin "2") (pinfunction "2_2") (pintype "passive"))
      (node (ref "C30") (pin "2") (pinfunction "2_2") (pintype "passive"))
      (node (ref "C31") (pin "2") (pinfunction "2_2") (pintype "passive"))
      (node (ref "C32") (pin "2") (pinfunction "2_2") (pintype "passive"))
      (node (ref "C33") (pin "2") (pinfunction "2_2") (pintype "passive"))
      (node (ref "C46") (pin "2") (pinfunction "2_2") (pintype "passive"))
      (node (ref "C47") (pin "2") (pinfunction "2_2") (pintype "passive"))
      (node (ref "C48") (pin "2") (pinfunction "2_2") (pintype "passive"))
      (node (ref "Q2") (pin "3") (pinfunction "S_3") (pintype "power_in"))
      (node (ref "R8") (pin "2") (pinfunction "2_2") (pintype "passive"))
      (node (ref "SICDIODE2") (pin "1") (pinfunction "G_1") (pintype "input"))
      (node (ref "SICDIODE2") (pin "3") (pinfunction "S_3") (pintype "power_in"))
      (node (ref "U$2") (pin "13") (pinfunction "GNDISO_13") (pintype "power_in"))
      (node (ref "U3") (pin "6") (pinfunction "0V_6") (pintype "bidirectional"))
      (node (ref "X3") (pin "A1") (pinfunction "-1_A1") (pintype "passive"))
      (node (ref "X3") (pin "A2") (pinfunction "-2_A2") (pintype "passive"))
    )
    (net (code "12") (name "GND_SIG2_2") (class "Default")
      (node (ref "C70") (pin "2") (pinfunction "2_2") (pintype "passive"))
      (node (ref "C71") (pin "2") (pinfunction "2_2") (pintype "passive"))
      (node (ref "C72") (pin "2") (pinfunction "2_2") (pintype "passive"))
      (node (ref "C73") (pin "2") (pinfunction "2_2") (pintype "passive"))
      (node (ref "C74") (pin "2") (pinfunction "2_2") (pintype "passive"))
      (node (ref "C75") (pin "2") (pinfunction "2_2") (pintype "passive"))
      (node (ref "C76") (pin "2") (pinfunction "2_2") (pintype "passive"))
      (node (ref "C77") (pin "2") (pinfunction "2_2") (pintype "passive"))
      (node (ref "C78") (pin "2") (pinfunction "2_2") (pintype "passive"))
      (node (ref "C79") (pin "2") (pinfunction "2_2") (pintype "passive"))
      (node (ref "C80") (pin "2") (pinfunction "2_2") (pintype "passive"))
      (node (ref "C92") (pin "2") (pinfunction "2_2") (pintype "passive"))
      (node (ref "C93") (pin "2") (pinfunction "2_2") (pintype "passive"))
      (node (ref "C94") (pin "2") (pinfunction "2_2") (pintype "passive"))
      (node (ref "Q4") (pin "3") (pinfunction "S_3") (pintype "power_in"))
      (node (ref "R44") (pin "2") (pinfunction "2_2") (pintype "passive"))
      (node (ref "SICDIODE3") (pin "1") (pinfunction "G_1") (pintype "input"))
      (node (ref "SICDIODE3") (pin "3") (pinfunction "S_3") (pintype "power_in"))
      (node (ref "U$1") (pin "13") (pinfunction "GNDISO_13") (pintype "power_in"))
      (node (ref "U4") (pin "6") (pinfunction "0V_6") (pintype "bidirectional"))
      (node (ref "X6") (pin "A1") (pinfunction "-1_A1") (pintype "passive"))
      (node (ref "X6") (pin "A2") (pinfunction "-2_A2") (pintype "passive"))
    )
    (net (code "13") (name "GND_SIG_2") (class "Default")
      (node (ref "C44") (pin "2") (pinfunction "2_2") (pintype "passive"))
      (node (ref "C49") (pin "2") (pinfunction "2_2") (pintype "passive"))
      (node (ref "C50") (pin "2") (pinfunction "2_2") (pintype "passive"))
      (node (ref "C51") (pin "2") (pinfunction "2_2") (pintype "passive"))
      (node (ref "C52") (pin "2") (pinfunction "2_2") (pintype "passive"))
      (node (ref "C53") (pin "2") (pinfunction "2_2") (pintype "passive"))
      (node (ref "C54") (pin "2") (pinfunction "2_2") (pintype "passive"))
      (node (ref "C55") (pin "2") (pinfunction "2_2") (pintype "passive"))
      (node (ref "C56") (pin "2") (pinfunction "2_2") (pintype "passive"))
      (node (ref "C57") (pin "2") (pinfunction "2_2") (pintype "passive"))
      (node (ref "C58") (pin "2") (pinfunction "2_2") (pintype "passive"))
      (node (ref "C91") (pin "2") (pinfunction "2_2") (pintype "passive"))
      (node (ref "D13") (pin "1") (pinfunction "K_1") (pintype "bidirectional"))
      (node (ref "D9-D.N.M.1") (pin "1") (pinfunction "K_1") (pintype "bidirectional"))
      (node (ref "Q3") (pin "3") (pinfunction "S_3") (pintype "power_in"))
      (node (ref "Q4") (pin "2") (pinfunction "D_2") (pintype "power_in"))
      (node (ref "R15") (pin "2") (pinfunction "2_2") (pintype "passive"))
      (node (ref "R58") (pin "2") (pinfunction "2_2") (pintype "passive"))
      (node (ref "SICDIODE1") (pin "1") (pinfunction "G_1") (pintype "input"))
      (node (ref "SICDIODE1") (pin "3") (pinfunction "S_3") (pintype "power_in"))
      (node (ref "SICDIODE3") (pin "2") (pinfunction "D_2") (pintype "power_in"))
      (node (ref "U$3") (pin "13") (pinfunction "GNDISO_13") (pintype "power_in"))
      (node (ref "U1") (pin "6") (pinfunction "0V_6") (pintype "bidirectional"))
      (node (ref "X5") (pin "A1") (pinfunction "-1_A1") (pintype "passive"))
      (node (ref "X5") (pin "A2") (pinfunction "-2_A2") (pintype "passive"))
    )
    (net (code "14") (name "GOFF") (class "Default")
      (node (ref "R3") (pin "1") (pinfunction "1_1") (pintype "passive"))
      (node (ref "R4") (pin "1") (pinfunction "1_1") (pintype "passive"))
      (node (ref "U$5") (pin "21") (pinfunction "GOFF_21") (pintype "power_in"))
    )
    (net (code "15") (name "GOFF2") (class "Default")
      (node (ref "R36") (pin "1") (pinfunction "1_1") (pintype "passive"))
      (node (ref "R37") (pin "1") (pinfunction "1_1") (pintype "passive"))
      (node (ref "U$2") (pin "21") (pinfunction "GOFF_21") (pintype "power_in"))
    )
    (net (code "16") (name "GOFF2_2") (class "Default")
      (node (ref "R53") (pin "1") (pinfunction "1_1") (pintype "passive"))
      (node (ref "R54") (pin "1") (pinfunction "1_1") (pintype "passive"))
      (node (ref "U$1") (pin "21") (pinfunction "GOFF_21") (pintype "power_in"))
    )
    (net (code "17") (name "GOFF_2") (class "Default")
      (node (ref "R40") (pin "1") (pinfunction "1_1") (pintype "passive"))
      (node (ref "R41") (pin "1") (pinfunction "1_1") (pintype "passive"))
      (node (ref "U$3") (pin "21") (pinfunction "GOFF_21") (pintype "power_in"))
    )
    (net (code "18") (name "GON") (class "Default")
      (node (ref "R5") (pin "1") (pinfunction "1_1") (pintype "passive"))
      (node (ref "R6") (pin "1") (pinfunction "1_1") (pintype "passive"))
      (node (ref "U$5") (pin "20") (pinfunction "GON_20") (pintype "power_in"))
    )
    (net (code "19") (name "GON2") (class "Default")
      (node (ref "R38") (pin "1") (pinfunction "1_1") (pintype "passive"))
      (node (ref "R39") (pin "1") (pinfunction "1_1") (pintype "passive"))
      (node (ref "U$2") (pin "20") (pinfunction "GON_20") (pintype "power_in"))
    )
    (net (code "20") (name "GON2_2") (class "Default")
      (node (ref "R55") (pin "1") (pinfunction "1_1") (pintype "passive"))
      (node (ref "R56") (pin "1") (pinfunction "1_1") (pintype "passive"))
      (node (ref "U$1") (pin "20") (pinfunction "GON_20") (pintype "power_in"))
    )
    (net (code "21") (name "GON_2") (class "Default")
      (node (ref "R42") (pin "1") (pinfunction "1_1") (pintype "passive"))
      (node (ref "R43") (pin "1") (pinfunction "1_1") (pintype "passive"))
      (node (ref "U$3") (pin "20") (pinfunction "GON_20") (pintype "power_in"))
    )
    (net (code "22") (name "IN+") (class "Default")
      (node (ref "DL3") (pin "C") (pinfunction "C_C") (pintype "passive"))
      (node (ref "J1") (pin "4") (pinfunction "4_4") (pintype "passive"))
      (node (ref "R13") (pin "1") (pinfunction "1_1") (pintype "passive"))
      (node (ref "R33") (pin "1") (pinfunction "1_1") (pintype "passive"))
    )
    (net (code "23") (name "IN+_2") (class "Default")
      (node (ref "DL7") (pin "C") (pinfunction "C_C") (pintype "passive"))
      (node (ref "J5") (pin "4") (pinfunction "4_4") (pintype "passive"))
      (node (ref "R24") (pin "1") (pinfunction "1_1") (pintype "passive"))
      (node (ref "R50") (pin "1") (pinfunction "1_1") (pintype "passive"))
    )
    (net (code "24") (name "IN+_PIN") (class "Default")
      (node (ref "C13") (pin "1") (pinfunction "1_1") (pintype "passive"))
      (node (ref "R13") (pin "2") (pinfunction "2_2") (pintype "passive"))
      (node (ref "U$5") (pin "9") (pinfunction "IN+_9") (pintype "input"))
    )
    (net (code "25") (name "IN+_PIN2") (class "Default")
      (node (ref "C40") (pin "1") (pinfunction "1_1") (pintype "passive"))
      (node (ref "R30") (pin "2") (pinfunction "2_2") (pintype "passive"))
      (node (ref "U$2") (pin "9") (pinfunction "IN+_9") (pintype "input"))
    )
    (net (code "26") (name "IN+_PIN2_2") (class "Default")
      (node (ref "C87") (pin "1") (pinfunction "1_1") (pintype "passive"))
      (node (ref "R47") (pin "2") (pinfunction "2_2") (pintype "passive"))
      (node (ref "U$1") (pin "9") (pinfunction "IN+_9") (pintype "input"))
    )
    (net (code "27") (name "IN+_PIN_2") (class "Default")
      (node (ref "C65") (pin "1") (pinfunction "1_1") (pintype "passive"))
      (node (ref "R24") (pin "2") (pinfunction "2_2") (pintype "passive"))
      (node (ref "U$3") (pin "9") (pinfunction "IN+_9") (pintype "input"))
    )
    (net (code "28") (name "IN-{slash}DIAG2") (class "Default")
      (node (ref "DL1") (pin "C") (pinfunction "C_C") (pintype "passive"))
      (node (ref "J1") (pin "5") (pinfunction "5_5") (pintype "passive"))
      (node (ref "R12") (pin "1") (pinfunction "1_1") (pintype "passive"))
      (node (ref "R30") (pin "1") (pinfunction "1_1") (pintype "passive"))
    )
    (net (code "29") (name "IN-{slash}DIAG2_2") (class "Default")
      (node (ref "DL5") (pin "C") (pinfunction "C_C") (pintype "passive"))
      (node (ref "J5") (pin "5") (pinfunction "5_5") (pintype "passive"))
      (node (ref "R27") (pin "1") (pinfunction "1_1") (pintype "passive"))
      (node (ref "R47") (pin "1") (pinfunction "1_1") (pintype "passive"))
    )
    (net (code "30") (name "IN-{slash}DIAG2_PIN") (class "Default")
      (node (ref "C9") (pin "1") (pinfunction "1_1") (pintype "passive"))
      (node (ref "R12") (pin "2") (pinfunction "2_2") (pintype "passive"))
      (node (ref "U$5") (pin "8") (pinfunction "IN-/DIAG2_8") (pintype "bidirectional"))
    )
    (net (code "31") (name "IN-{slash}DIAG2_PIN2") (class "Default")
      (node (ref "C42") (pin "1") (pinfunction "1_1") (pintype "passive"))
      (node (ref "R33") (pin "2") (pinfunction "2_2") (pintype "passive"))
      (node (ref "U$2") (pin "8") (pinfunction "IN-/DIAG2_8") (pintype "bidirectional"))
    )
    (net (code "32") (name "IN-{slash}DIAG2_PIN2_2") (class "Default")
      (node (ref "C89") (pin "1") (pinfunction "1_1") (pintype "passive"))
      (node (ref "R50") (pin "2") (pinfunction "2_2") (pintype "passive"))
      (node (ref "U$1") (pin "8") (pinfunction "IN-/DIAG2_8") (pintype "bidirectional"))
    )
    (net (code "33") (name "IN-{slash}DIAG2_PIN_2") (class "Default")
      (node (ref "C67") (pin "1") (pinfunction "1_1") (pintype "passive"))
      (node (ref "R27") (pin "2") (pinfunction "2_2") (pintype "passive"))
      (node (ref "U$3") (pin "8") (pinfunction "IN-/DIAG2_8") (pintype "bidirectional"))
    )
    (net (code "34") (name "N$8") (class "Default")
      (node (ref "D1") (pin "3") (pinfunction "COM_3") (pintype "bidirectional"))
      (node (ref "Q1") (pin "1") (pinfunction "G_1") (pintype "input"))
      (node (ref "R2") (pin "1") (pinfunction "1_1") (pintype "passive"))
      (node (ref "R3") (pin "2") (pinfunction "2_2") (pintype "passive"))
      (node (ref "R4") (pin "2") (pinfunction "2_2") (pintype "passive"))
      (node (ref "R5") (pin "2") (pinfunction "2_2") (pintype "passive"))
      (node (ref "R6") (pin "2") (pinfunction "2_2") (pintype "passive"))
      (node (ref "R7") (pin "1") (pinfunction "1_1") (pintype "passive"))
      (node (ref "TP2") (pin "TP") (pinfunction "TP_TP") (pintype "input"))
      (node (ref "U$5") (pin "22") (pinfunction "CLAMP_22") (pintype "power_in"))
    )
    (net (code "35") (name "N$8_2") (class "Default")
      (node (ref "D11") (pin "3") (pinfunction "COM_3") (pintype "bidirectional"))
      (node (ref "Q3") (pin "1") (pinfunction "G_1") (pintype "input"))
      (node (ref "R18") (pin "1") (pinfunction "1_1") (pintype "passive"))
      (node (ref "R29") (pin "1") (pinfunction "1_1") (pintype "passive"))
      (node (ref "R40") (pin "2") (pinfunction "2_2") (pintype "passive"))
      (node (ref "R41") (pin "2") (pinfunction "2_2") (pintype "passive"))
      (node (ref "R42") (pin "2") (pinfunction "2_2") (pintype "passive"))
      (node (ref "R43") (pin "2") (pinfunction "2_2") (pintype "passive"))
      (node (ref "TP7") (pin "TP") (pinfunction "TP_TP") (pintype "input"))
      (node (ref "U$3") (pin "22") (pinfunction "CLAMP_22") (pintype "power_in"))
    )
    (net (code "36") (name "N$21") (class "Default")
      (node (ref "C47") (pin "1") (pinfunction "1_1") (pintype "passive"))
      (node (ref "C48") (pin "1") (pinfunction "1_1") (pintype "passive"))
      (node (ref "D5") (pin "1") (pinfunction "K_1") (pintype "bidirectional"))
      (node (ref "D9-D.N.M") (pin "1") (pinfunction "K_1") (pintype "bidirectional"))
      (node (ref "Q1") (pin "2") (pinfunction "D_2") (pintype "power_in"))
      (node (ref "R20") (pin "2") (pinfunction "2_2") (pintype "passive"))
      (node (ref "SICDIODE") (pin "2") (pinfunction "D_2") (pintype "power_in"))
      (node (ref "TP1") (pin "TP") (pinfunction "TP_TP") (pintype "input"))
      (node (ref "X1") (pin "A1") (pinfunction "-1_A1") (pintype "passive"))
      (node (ref "X1") (pin "A2") (pinfunction "-2_A2") (pintype "passive"))
    )
    (net (code "37") (name "N$21_2") (class "Default")
      (node (ref "C93") (pin "1") (pinfunction "1_1") (pintype "passive"))
      (node (ref "C94") (pin "1") (pinfunction "1_1") (pintype "passive"))
      (node (ref "D9") (pin "1") (pinfunction "K_1") (pintype "bidirectional"))
      (node (ref "D9-D.N.M1") (pin "1") (pinfunction "K_1") (pintype "bidirectional"))
      (node (ref "Q3") (pin "2") (pinfunction "D_2") (pintype "power_in"))
      (node (ref "R57") (pin "2") (pinfunction "2_2") (pintype "passive"))
      (node (ref "SICDIODE1") (pin "2") (pinfunction "D_2") (pintype "power_in"))
      (node (ref "TP3") (pin "TP") (pinfunction "TP_TP") (pintype "input"))
      (node (ref "X4") (pin "A1") (pinfunction "-1_A1") (pintype "passive"))
      (node (ref "X4") (pin "A2") (pinfunction "-2_A2") (pintype "passive"))
    )
    (net (code "38") (name "N$82") (class "Default")
      (node (ref "D7") (pin "3") (pinfunction "COM_3") (pintype "bidirectional"))
      (node (ref "Q2") (pin "1") (pinfunction "G_1") (pintype "input"))
      (node (ref "R23") (pin "1") (pinfunction "1_1") (pintype "passive"))
      (node (ref "R35") (pin "1") (pinfunction "1_1") (pintype "passive"))
      (node (ref "R36") (pin "2") (pinfunction "2_2") (pintype "passive"))
      (node (ref "R37") (pin "2") (pinfunction "2_2") (pintype "passive"))
      (node (ref "R38") (pin "2") (pinfunction "2_2") (pintype "passive"))
      (node (ref "R39") (pin "2") (pinfunction "2_2") (pintype "passive"))
      (node (ref "TP4") (pin "TP") (pinfunction "TP_TP") (pintype "input"))
      (node (ref "U$2") (pin "22") (pinfunction "CLAMP_22") (pintype "power_in"))
    )
    (net (code "39") (name "N$82_2") (class "Default")
      (node (ref "D15") (pin "3") (pinfunction "COM_3") (pintype "bidirectional"))
      (node (ref "Q4") (pin "1") (pinfunction "G_1") (pintype "input"))
      (node (ref "R46") (pin "1") (pinfunction "1_1") (pintype "passive"))
      (node (ref "R52") (pin "1") (pinfunction "1_1") (pintype "passive"))
      (node (ref "R53") (pin "2") (pinfunction "2_2") (pintype "passive"))
      (node (ref "R54") (pin "2") (pinfunction "2_2") (pintype "passive"))
      (node (ref "R55") (pin "2") (pinfunction "2_2") (pintype "passive"))
      (node (ref "R56") (pin "2") (pinfunction "2_2") (pintype "passive"))
      (node (ref "TP8") (pin "TP") (pinfunction "TP_TP") (pintype "input"))
      (node (ref "U$1") (pin "22") (pinfunction "CLAMP_22") (pintype "power_in"))
    )
    (net (code "40") (name "NONE") (class "Default")
      (node (ref "J2") (pin "1") (pinfunction "1_1") (pintype "passive"))
    )
    (net (code "41") (name "NONE_2") (class "Default")
      (node (ref "J6") (pin "1") (pinfunction "1_1") (pintype "passive"))
    )
    (net (code "42") (name "Net-(C45-Pad1)") (class "Default")
      (node (ref "C45") (pin "1") (pinfunction "1_1") (pintype "passive"))
      (node (ref "R20") (pin "1") (pinfunction "1_1") (pintype "passive"))
    )
    (net (code "43") (name "Net-(C46-Pad1)") (class "Default")
      (node (ref "C46") (pin "1") (pinfunction "1_1") (pintype "passive"))
      (node (ref "R21") (pin "1") (pinfunction "1_1") (pintype "passive"))
    )
    (net (code "44") (name "Net-(C91-Pad1)") (class "Default")
      (node (ref "C91") (pin "1") (pinfunction "1_1") (pintype "passive"))
      (node (ref "R57") (pin "1") (pinfunction "1_1") (pintype "passive"))
    )
    (net (code "45") (name "Net-(C92-Pad1)") (class "Default")
      (node (ref "C92") (pin "1") (pinfunction "1_1") (pintype "passive"))
      (node (ref "R58") (pin "1") (pinfunction "1_1") (pintype "passive"))
    )
    (net (code "46") (name "Net-(D2-A)") (class "Default")
      (node (ref "D2") (pin "2") (pinfunction "A_2") (pintype "bidirectional"))
      (node (ref "R22") (pin "2") (pinfunction "2_2") (pintype "passive"))
    )
    (net (code "47") (name "Net-(D3-A)") (class "Default")
      (node (ref "D3") (pin "2") (pinfunction "A_2") (pintype "bidirectional"))
      (node (ref "D4") (pin "2") (pinfunction "A_2") (pintype "bidirectional"))
      (node (ref "D9-D.N.M") (pin "2") (pinfunction "A_2") (pintype "bidirectional"))
    )
    (net (code "48") (name "Net-(D3-K)") (class "Default")
      (node (ref "D3") (pin "1") (pinfunction "K_1") (pintype "bidirectional"))
      (node (ref "R2") (pin "2") (pinfunction "2_2") (pintype "passive"))
    )
    (net (code "49") (name "Net-(D4-K)") (class "Default")
      (node (ref "D4") (pin "1") (pinfunction "K_1") (pintype "bidirectional"))
      (node (ref "R15-D.N.M") (pin "1") (pinfunction "1_1") (pintype "passive"))
    )
    (net (code "50") (name "Net-(D5-A)") (class "Default")
      (node (ref "D5") (pin "2") (pinfunction "A_2") (pintype "bidirectional"))
      (node (ref "R10") (pin "2") (pinfunction "2_2") (pintype "passive"))
    )
    (net (code "51") (name "Net-(D6-A)") (class "Default")
      (node (ref "D6") (pin "2") (pinfunction "A_2") (pintype "bidirectional"))
      (node (ref "D8") (pin "2") (pinfunction "A_2") (pintype "bidirectional"))
      (node (ref "D9-D.N.M.2") (pin "2") (pinfunction "A_2") (pintype "bidirectional"))
    )
    (net (code "52") (name "Net-(D6-K)") (class "Default")
      (node (ref "D6") (pin "1") (pinfunction "K_1") (pintype "bidirectional"))
      (node (ref "R1-D.N.M.2") (pin "1") (pinfunction "1_1") (pintype "passive"))
    )
    (net (code "53") (name "Net-(D8-K)") (class "Default")
      (node (ref "D8") (pin "1") (pinfunction "K_1") (pintype "bidirectional"))
      (node (ref "R35") (pin "2") (pinfunction "2_2") (pintype "passive"))
    )
    (net (code "54") (name "Net-(D9-A)") (class "Default")
      (node (ref "D9") (pin "2") (pinfunction "A_2") (pintype "bidirectional"))
      (node (ref "R17") (pin "2") (pinfunction "2_2") (pintype "passive"))
    )
    (net (code "55") (name "Net-(D10-A)") (class "Default")
      (node (ref "D10") (pin "2") (pinfunction "A_2") (pintype "bidirectional"))
      (node (ref "D12") (pin "2") (pinfunction "A_2") (pintype "bidirectional"))
      (node (ref "D9-D.N.M1") (pin "2") (pinfunction "A_2") (pintype "bidirectional"))
    )
    (net (code "56") (name "Net-(D10-K)") (class "Default")
      (node (ref "D10") (pin "1") (pinfunction "K_1") (pintype "bidirectional"))
      (node (ref "R15-D.N.M1") (pin "1") (pinfunction "1_1") (pintype "passive"))
    )
    (net (code "57") (name "Net-(D12-K)") (class "Default")
      (node (ref "D12") (pin "1") (pinfunction "K_1") (pintype "bidirectional"))
      (node (ref "R29") (pin "2") (pinfunction "2_2") (pintype "passive"))
    )
    (net (code "58") (name "Net-(D13-A)") (class "Default")
      (node (ref "D13") (pin "2") (pinfunction "A_2") (pintype "bidirectional"))
      (node (ref "R45") (pin "2") (pinfunction "2_2") (pintype "passive"))
    )
    (net (code "59") (name "Net-(D14-A)") (class "Default")
      (node (ref "D14") (pin "2") (pinfunction "A_2") (pintype "bidirectional"))
      (node (ref "D16") (pin "2") (pinfunction "A_2") (pintype "bidirectional"))
      (node (ref "D9-D.N.M.1") (pin "2") (pinfunction "A_2") (pintype "bidirectional"))
    )
    (net (code "60") (name "Net-(D14-K)") (class "Default")
      (node (ref "D14") (pin "1") (pinfunction "K_1") (pintype "bidirectional"))
      (node (ref "R1-D.N.M.1") (pin "1") (pinfunction "1_1") (pintype "passive"))
    )
    (net (code "61") (name "Net-(D16-K)") (class "Default")
      (node (ref "D16") (pin "1") (pinfunction "K_1") (pintype "bidirectional"))
      (node (ref "R52") (pin "2") (pinfunction "2_2") (pintype "passive"))
    )
    (net (code "62") (name "Net-(DL1-PadA)") (class "Default")
      (node (ref "DL1") (pin "A") (pinfunction "A_A") (pintype "passive"))
      (node (ref "R11") (pin "1") (pinfunction "1_1") (pintype "passive"))
    )
    (net (code "63") (name "Net-(DL2-PadA)") (class "Default")
      (node (ref "DL2") (pin "A") (pinfunction "A_A") (pintype "passive"))
      (node (ref "R14") (pin "1") (pinfunction "1_1") (pintype "passive"))
    )
    (net (code "64") (name "Net-(DL3-PadA)") (class "Default")
      (node (ref "DL3") (pin "A") (pinfunction "A_A") (pintype "passive"))
      (node (ref "R31") (pin "1") (pinfunction "1_1") (pintype "passive"))
    )
    (net (code "65") (name "Net-(DL4-PadA)") (class "Default")
      (node (ref "DL4") (pin "A") (pinfunction "A_A") (pintype "passive"))
      (node (ref "R32") (pin "1") (pinfunction "1_1") (pintype "passive"))
    )
    (net (code "66") (name "Net-(DL5-PadA)") (class "Default")
      (node (ref "DL5") (pin "A") (pinfunction "A_A") (pintype "passive"))
      (node (ref "R25") (pin "1") (pinfunction "1_1") (pintype "passive"))
    )
    (net (code "67") (name "Net-(DL6-PadA)") (class "Default")
      (node (ref "DL6") (pin "A") (pinfunction "A_A") (pintype "passive"))
      (node (ref "R26") (pin "1") (pinfunction "1_1") (pintype "passive"))
    )
    (net (code "68") (name "Net-(DL7-PadA)") (class "Default")
      (node (ref "DL7") (pin "A") (pinfunction "A_A") (pintype "passive"))
      (node (ref "R48") (pin "1") (pinfunction "1_1") (pintype "passive"))
    )
    (net (code "69") (name "Net-(DL8-PadA)") (class "Default")
      (node (ref "DL8") (pin "A") (pinfunction "A_A") (pintype "passive"))
      (node (ref "R49") (pin "1") (pinfunction "1_1") (pintype "passive"))
    )
    (net (code "70") (name "Net-(IC1-VIN)") (class "Default")
      (node (ref "C6") (pin "1") (pinfunction "1_1") (pintype "passive"))
      (node (ref "IC1") (pin "1") (pinfunction "VIN_1") (pintype "input"))
      (node (ref "MICROCONTROLLER_POWER1") (pin "2") (pinfunction "2_2") (pintype "passive"))
    )
    (net (code "71") (name "Net-(U$1-ASC)") (class "Default")
      (node (ref "R44") (pin "1") (pinfunction "1_1") (pintype "passive"))
      (node (ref "U$1") (pin "24") (pinfunction "ASC_24") (pintype "power_in"))
    )
    (net (code "72") (name "Net-(U$2-ASC)") (class "Default")
      (node (ref "R8") (pin "1") (pinfunction "1_1") (pintype "passive"))
      (node (ref "U$2") (pin "24") (pinfunction "ASC_24") (pintype "power_in"))
    )
    (net (code "73") (name "Net-(U$3-ASC)") (class "Default")
      (node (ref "R15") (pin "1") (pinfunction "1_1") (pintype "passive"))
      (node (ref "U$3") (pin "24") (pinfunction "ASC_24") (pintype "power_in"))
    )
    (net (code "74") (name "Net-(U$5-ASC)") (class "Default")
      (node (ref "R1") (pin "1") (pinfunction "1_1") (pintype "passive"))
      (node (ref "U$5") (pin "24") (pinfunction "ASC_24") (pintype "power_in"))
    )
    (net (code "75") (name "SD") (class "Default")
      (node (ref "J1") (pin "2") (pinfunction "2_2") (pintype "passive"))
      (node (ref "R16") (pin "1") (pinfunction "1_1") (pintype "passive"))
    )
    (net (code "76") (name "SDI") (class "Default")
      (node (ref "J1") (pin "9") (pinfunction "9_9") (pintype "passive"))
      (node (ref "SJ2") (pin "2") (pinfunction "2_2") (pintype "passive"))
    )
    (net (code "77") (name "SDI2") (class "Default")
      (node (ref "SJ5") (pin "2") (pinfunction "2_2") (pintype "passive"))
      (node (ref "SJ7") (pin "2") (pinfunction "2_2") (pintype "passive"))
    )
    (net (code "78") (name "SDI2_2") (class "Default")
      (node (ref "SJ11") (pin "2") (pinfunction "2_2") (pintype "passive"))
      (node (ref "SJ8") (pin "2") (pinfunction "2_2") (pintype "passive"))
    )
    (net (code "79") (name "SDI_2") (class "Default")
      (node (ref "J5") (pin "9") (pinfunction "9_9") (pintype "passive"))
      (node (ref "SJ9") (pin "2") (pinfunction "2_2") (pintype "passive"))
    )
    (net (code "80") (name "SDI_PIN") (class "Default")
      (node (ref "C23") (pin "1") (pinfunction "1_1") (pintype "passive"))
      (node (ref "J3") (pin "4") (pinfunction "4_4") (pintype "passive"))
      (node (ref "SJ2") (pin "1") (pinfunction "1_1") (pintype "passive"))
      (node (ref "U$5") (pin "3") (pinfunction "SDI_3") (pintype "input"))
    )
    (net (code "81") (name "SDI_PIN2") (class "Default")
      (node (ref "C39") (pin "1") (pinfunction "1_1") (pintype "passive"))
      (node (ref "SJ7") (pin "1") (pinfunction "1_1") (pintype "passive"))
      (node (ref "U$2") (pin "3") (pinfunction "SDI_3") (pintype "input"))
    )
    (net (code "82") (name "SDI_PIN2_2") (class "Default")
      (node (ref "C86") (pin "1") (pinfunction "1_1") (pintype "passive"))
      (node (ref "SJ11") (pin "1") (pinfunction "1_1") (pintype "passive"))
      (node (ref "U$1") (pin "3") (pinfunction "SDI_3") (pintype "input"))
    )
    (net (code "83") (name "SDO") (class "Default")
      (node (ref "J1") (pin "10") (pinfunction "10_10") (pintype "passive"))
      (node (ref "SJ1") (pin "1") (pinfunction "1_1") (pintype "passive"))
    )
    (net (code "84") (name "SDO_2") (class "Default")
      (node (ref "J5") (pin "10") (pinfunction "10_10") (pintype "passive"))
      (node (ref "SJ12") (pin "1") (pinfunction "1_1") (pintype "passive"))
    )
    (net (code "85") (name "SDO_PIN") (class "Default")
      (node (ref "SJ5") (pin "1") (pinfunction "1_1") (pintype "passive"))
      (node (ref "U$5") (pin "2") (pinfunction "SDO_2") (pintype "bidirectional"))
    )
    (net (code "86") (name "SDO_PIN2") (class "Default")
      (node (ref "C64") (pin "1") (pinfunction "1_1") (pintype "passive"))
      (node (ref "J4") (pin "4") (pinfunction "4_4") (pintype "passive"))
      (node (ref "J7") (pin "4") (pinfunction "4_4") (pintype "passive"))
      (node (ref "SJ1") (pin "2") (pinfunction "2_2") (pintype "passive"))
      (node (ref "SJ9") (pin "1") (pinfunction "1_1") (pintype "passive"))
      (node (ref "U$2") (pin "2") (pinfunction "SDO_2") (pintype "bidirectional"))
      (node (ref "U$3") (pin "3") (pinfunction "SDI_3") (pintype "input"))
    )
    (net (code "87") (name "SDO_PIN2_2") (class "Default")
      (node (ref "J8") (pin "4") (pinfunction "4_4") (pintype "passive"))
      (node (ref "SJ12") (pin "2") (pinfunction "2_2") (pintype "passive"))
      (node (ref "U$1") (pin "2") (pinfunction "SDO_2") (pintype "bidirectional"))
    )
    (net (code "88") (name "SDO_PIN_2") (class "Default")
      (node (ref "SJ8") (pin "1") (pinfunction "1_1") (pintype "passive"))
      (node (ref "U$3") (pin "2") (pinfunction "SDO_2") (pintype "bidirectional"))
    )
    (net (code "89") (name "SD_2") (class "Default")
      (node (ref "J5") (pin "2") (pinfunction "2_2") (pintype "passive"))
      (node (ref "R19") (pin "1") (pinfunction "1_1") (pintype "passive"))
    )
    (net (code "90") (name "SD_PIN") (class "Default")
      (node (ref "C15") (pin "1") (pinfunction "1_1") (pintype "passive"))
      (node (ref "C41") (pin "1") (pinfunction "1_1") (pintype "passive"))
      (node (ref "J3") (pin "1") (pinfunction "1_1") (pintype "passive"))
      (node (ref "J4") (pin "1") (pinfunction "1_1") (pintype "passive"))
      (node (ref "R16") (pin "2") (pinfunction "2_2") (pintype "passive"))
      (node (ref "U$2") (pin "11") (pinfunction "/SD_11") (pintype "input"))
      (node (ref "U$5") (pin "11") (pinfunction "/SD_11") (pintype "input"))
    )
    (net (code "91") (name "SD_PIN_2") (class "Default")
      (node (ref "C66") (pin "1") (pinfunction "1_1") (pintype "passive"))
      (node (ref "C88") (pin "1") (pinfunction "1_1") (pintype "passive"))
      (node (ref "J7") (pin "1") (pinfunction "1_1") (pintype "passive"))
      (node (ref "J8") (pin "1") (pinfunction "1_1") (pintype "passive"))
      (node (ref "R19") (pin "2") (pinfunction "2_2") (pintype "passive"))
      (node (ref "U$1") (pin "11") (pinfunction "/SD_11") (pintype "input"))
      (node (ref "U$3") (pin "11") (pinfunction "/SD_11") (pintype "input"))
    )
    (net (code "92") (name "SENSE") (class "Default")
      (node (ref "C12") (pin "1") (pinfunction "1_1") (pintype "passive"))
      (node (ref "TP5") (pin "TP") (pinfunction "TP_TP") (pintype "input"))
      (node (ref "U$5") (pin "16") (pinfunction "SENSE_16") (pintype "power_in"))
    )
    (net (code "93") (name "SENSE2") (class "Default")
      (node (ref "C24") (pin "1") (pinfunction "1_1") (pintype "passive"))
      (node (ref "TP6") (pin "TP") (pinfunction "TP_TP") (pintype "input"))
      (node (ref "U$2") (pin "16") (pinfunction "SENSE_16") (pintype "power_in"))
    )
    (net (code "94") (name "SENSE2_2") (class "Default")
      (node (ref "C71") (pin "1") (pinfunction "1_1") (pintype "passive"))
      (node (ref "TP10") (pin "TP") (pinfunction "TP_TP") (pintype "input"))
      (node (ref "U$1") (pin "16") (pinfunction "SENSE_16") (pintype "power_in"))
    )
    (net (code "95") (name "SENSE_2") (class "Default")
      (node (ref "C49") (pin "1") (pinfunction "1_1") (pintype "passive"))
      (node (ref "TP9") (pin "TP") (pinfunction "TP_TP") (pintype "input"))
      (node (ref "U$3") (pin "16") (pinfunction "SENSE_16") (pintype "power_in"))
    )
    (net (code "96") (name "VCECLAMP") (class "Default")
      (node (ref "R15-D.N.M") (pin "2") (pinfunction "2_2") (pintype "passive"))
      (node (ref "R9") (pin "2") (pinfunction "2_2") (pintype "passive"))
      (node (ref "U$5") (pin "19") (pinfunction "VCECLAMP_19") (pintype "power_in"))
    )
    (net (code "97") (name "VCECLAMP2") (class "Default")
      (node (ref "R1-D.N.M.2") (pin "2") (pinfunction "2_2") (pintype "passive"))
      (node (ref "R34") (pin "2") (pinfunction "2_2") (pintype "passive"))
      (node (ref "U$2") (pin "19") (pinfunction "VCECLAMP_19") (pintype "power_in"))
    )
    (net (code "98") (name "VCECLAMP2_2") (class "Default")
      (node (ref "R1-D.N.M.1") (pin "2") (pinfunction "2_2") (pintype "passive"))
      (node (ref "R51") (pin "2") (pinfunction "2_2") (pintype "passive"))
      (node (ref "U$1") (pin "19") (pinfunction "VCECLAMP_19") (pintype "power_in"))
    )
    (net (code "99") (name "VCECLAMP_2") (class "Default")
      (node (ref "R15-D.N.M1") (pin "2") (pinfunction "2_2") (pintype "passive"))
      (node (ref "R28") (pin "2") (pinfunction "2_2") (pintype "passive"))
      (node (ref "U$3") (pin "19") (pinfunction "VCECLAMP_19") (pintype "power_in"))
    )
    (net (code "100") (name "VDD") (class "Default")
      (node (ref "C36") (pin "1") (pinfunction "1_1") (pintype "passive"))
      (node (ref "C4") (pin "1") (pinfunction "1_1") (pintype "passive"))
      (node (ref "C43") (pin "1") (pinfunction "1_1") (pintype "passive"))
      (node (ref "C61") (pin "1") (pinfunction "1_1") (pintype "passive"))
      (node (ref "C7") (pin "1") (pinfunction "1_1") (pintype "passive"))
      (node (ref "C83") (pin "1") (pinfunction "1_1") (pintype "passive"))
      (node (ref "IC1") (pin "3") (pinfunction "VO_3") (pintype "passive"))
      (node (ref "IC2") (pin "24") (pinfunction "VDD_1_24") (pintype "power_in"))
      (node (ref "IC2") (pin "36") (pinfunction "VDD_2_36") (pintype "power_in"))
      (node (ref "IC2") (pin "48") (pinfunction "VDD_3_48") (pintype "power_in"))
      (node (ref "IC2") (pin "9") (pinfunction "VDDA_9") (pintype "power_in"))
      (node (ref "IC3") (pin "11") (pinfunction "VDD_11") (pintype "bidirectional"))
      (node (ref "J1") (pin "12") (pinfunction "12_12") (pintype "passive"))
      (node (ref "J1") (pin "8") (pinfunction "8_8") (pintype "passive"))
      (node (ref "J5") (pin "12") (pinfunction "12_12") (pintype "passive"))
      (node (ref "J5") (pin "8") (pinfunction "8_8") (pintype "passive"))
      (node (ref "R11") (pin "2") (pinfunction "2_2") (pintype "passive"))
      (node (ref "R14") (pin "2") (pinfunction "2_2") (pintype "passive"))
      (node (ref "R25") (pin "2") (pinfunction "2_2") (pintype "passive"))
      (node (ref "R26") (pin "2") (pinfunction "2_2") (pintype "passive"))
      (node (ref "R31") (pin "2") (pinfunction "2_2") (pintype "passive"))
      (node (ref "R32") (pin "2") (pinfunction "2_2") (pintype "passive"))
      (node (ref "R48") (pin "2") (pinfunction "2_2") (pintype "passive"))
      (node (ref "R49") (pin "2") (pinfunction "2_2") (pintype "passive"))
      (node (ref "SJ10") (pin "2") (pinfunction "2_2") (pintype "passive"))
      (node (ref "SJ3") (pin "2") (pinfunction "2_2") (pintype "passive"))
      (node (ref "SJ4") (pin "2") (pinfunction "2_2") (pintype "passive"))
      (node (ref "SJ6") (pin "2") (pinfunction "2_2") (pintype "passive"))
      (node (ref "U$1") (pin "7") (pinfunction "VDD_7") (pintype "power_in"))
      (node (ref "U$2") (pin "7") (pinfunction "VDD_7") (pintype "power_in"))
      (node (ref "U$3") (pin "7") (pinfunction "VDD_7") (pintype "power_in"))
      (node (ref "U$5") (pin "7") (pinfunction "VDD_7") (pintype "power_in"))
      (node (ref "U1") (pin "1") (pinfunction "+VIN_1") (pintype "bidirectional"))
      (node (ref "U2") (pin "1") (pinfunction "+VIN_1") (pintype "bidirectional"))
      (node (ref "U3") (pin "1") (pinfunction "+VIN_1") (pintype "bidirectional"))
      (node (ref "U4") (pin "1") (pinfunction "+VIN_1") (pintype "bidirectional"))
    )
    (net (code "101") (name "VH") (class "Default")
      (node (ref "C10") (pin "1") (pinfunction "1_1") (pintype "passive"))
      (node (ref "C18") (pin "1") (pinfunction "1_1") (pintype "passive"))
      (node (ref "C2") (pin "1") (pinfunction "1_1") (pintype "passive"))
      (node (ref "D1") (pin "2") (pinfunction "K_2") (pintype "bidirectional"))
      (node (ref "U$5") (pin "17") (pinfunction "VH_17") (pintype "power_in"))
      (node (ref "U2") (pin "7") (pinfunction "+VOUT_7") (pintype "bidirectional"))
    )
    (net (code "102") (name "VH2") (class "Default")
      (node (ref "C29") (pin "1") (pinfunction "1_1") (pintype "passive"))
      (node (ref "C31") (pin "1") (pinfunction "1_1") (pintype "passive"))
      (node (ref "C32") (pin "1") (pinfunction "1_1") (pintype "passive"))
      (node (ref "D7") (pin "2") (pinfunction "K_2") (pintype "bidirectional"))
      (node (ref "U$2") (pin "17") (pinfunction "VH_17") (pintype "power_in"))
      (node (ref "U3") (pin "7") (pinfunction "+VOUT_7") (pintype "bidirectional"))
    )
    (net (code "103") (name "VH2_2") (class "Default")
      (node (ref "C76") (pin "1") (pinfunction "1_1") (pintype "passive"))
      (node (ref "C78") (pin "1") (pinfunction "1_1") (pintype "passive"))
      (node (ref "C79") (pin "1") (pinfunction "1_1") (pintype "passive"))
      (node (ref "D15") (pin "2") (pinfunction "K_2") (pintype "bidirectional"))
      (node (ref "U$1") (pin "17") (pinfunction "VH_17") (pintype "power_in"))
      (node (ref "U4") (pin "7") (pinfunction "+VOUT_7") (pintype "bidirectional"))
    )
    (net (code "104") (name "VH_2") (class "Default")
      (node (ref "C54") (pin "1") (pinfunction "1_1") (pintype "passive"))
      (node (ref "C56") (pin "1") (pinfunction "1_1") (pintype "passive"))
      (node (ref "C57") (pin "1") (pinfunction "1_1") (pintype "passive"))
      (node (ref "D11") (pin "2") (pinfunction "K_2") (pintype "bidirectional"))
      (node (ref "U$3") (pin "17") (pinfunction "VH_17") (pintype "power_in"))
      (node (ref "U1") (pin "7") (pinfunction "+VOUT_7") (pintype "bidirectional"))
    )
    (net (code "105") (name "VL") (class "Default")
      (node (ref "C1") (pin "1") (pinfunction "1_1") (pintype "passive"))
      (node (ref "C16") (pin "1") (pinfunction "1_1") (pintype "passive"))
      (node (ref "C17") (pin "1") (pinfunction "1_1") (pintype "passive"))
      (node (ref "C3") (pin "1") (pinfunction "1_1") (pintype "passive"))
      (node (ref "D1") (pin "1") (pinfunction "A_1") (pintype "bidirectional"))
      (node (ref "R7") (pin "2") (pinfunction "2_2") (pintype "passive"))
      (node (ref "R9") (pin "1") (pinfunction "1_1") (pintype "passive"))
      (node (ref "U$5") (pin "14") (pinfunction "VL_14") (pintype "power_in"))
      (node (ref "U$5") (pin "23") (pinfunction "VL_23") (pintype "power_in"))
      (node (ref "U2") (pin "5") (pinfunction "-VOUT_5") (pintype "bidirectional"))
    )
    (net (code "106") (name "VL2") (class "Default")
      (node (ref "C27") (pin "1") (pinfunction "1_1") (pintype "passive"))
      (node (ref "C28") (pin "1") (pinfunction "1_1") (pintype "passive"))
      (node (ref "C30") (pin "1") (pinfunction "1_1") (pintype "passive"))
      (node (ref "C33") (pin "1") (pinfunction "1_1") (pintype "passive"))
      (node (ref "D7") (pin "1") (pinfunction "A_1") (pintype "bidirectional"))
      (node (ref "R23") (pin "2") (pinfunction "2_2") (pintype "passive"))
      (node (ref "R34") (pin "1") (pinfunction "1_1") (pintype "passive"))
      (node (ref "U$2") (pin "14") (pinfunction "VL_14") (pintype "power_in"))
      (node (ref "U$2") (pin "23") (pinfunction "VL_23") (pintype "power_in"))
      (node (ref "U3") (pin "5") (pinfunction "-VOUT_5") (pintype "bidirectional"))
    )
    (net (code "107") (name "VL2_2") (class "Default")
      (node (ref "C74") (pin "1") (pinfunction "1_1") (pintype "passive"))
      (node (ref "C75") (pin "1") (pinfunction "1_1") (pintype "passive"))
      (node (ref "C77") (pin "1") (pinfunction "1_1") (pintype "passive"))
      (node (ref "C80") (pin "1") (pinfunction "1_1") (pintype "passive"))
      (node (ref "D15") (pin "1") (pinfunction "A_1") (pintype "bidirectional"))
      (node (ref "R46") (pin "2") (pinfunction "2_2") (pintype "passive"))
      (node (ref "R51") (pin "1") (pinfunction "1_1") (pintype "passive"))
      (node (ref "U$1") (pin "14") (pinfunction "VL_14") (pintype "power_in"))
      (node (ref "U$1") (pin "23") (pinfunction "VL_23") (pintype "power_in"))
      (node (ref "U4") (pin "5") (pinfunction "-VOUT_5") (pintype "bidirectional"))
    )
    (net (code "108") (name "VL_2") (class "Default")
      (node (ref "C52") (pin "1") (pinfunction "1_1") (pintype "passive"))
      (node (ref "C53") (pin "1") (pinfunction "1_1") (pintype "passive"))
      (node (ref "C55") (pin "1") (pinfunction "1_1") (pintype "passive"))
      (node (ref "C58") (pin "1") (pinfunction "1_1") (pintype "passive"))
      (node (ref "D11") (pin "1") (pinfunction "A_1") (pintype "bidirectional"))
      (node (ref "R18") (pin "2") (pinfunction "2_2") (pintype "passive"))
      (node (ref "R28") (pin "1") (pinfunction "1_1") (pintype "passive"))
      (node (ref "U$3") (pin "14") (pinfunction "VL_14") (pintype "power_in"))
      (node (ref "U$3") (pin "23") (pinfunction "VL_23") (pintype "power_in"))
      (node (ref "U1") (pin "5") (pinfunction "-VOUT_5") (pintype "bidirectional"))
    )
    (net (code "109") (name "VREG") (class "Default")
      (node (ref "C19") (pin "1") (pinfunction "1_1") (pintype "passive"))
      (node (ref "C34") (pin "1") (pinfunction "1_1") (pintype "passive"))
      (node (ref "C35") (pin "1") (pinfunction "1_1") (pintype "passive"))
      (node (ref "C5") (pin "1") (pinfunction "1_1") (pintype "passive"))
      (node (ref "SJ3") (pin "1") (pinfunction "1_1") (pintype "passive"))
      (node (ref "SJ6") (pin "1") (pinfunction "1_1") (pintype "passive"))
      (node (ref "U$2") (pin "6") (pinfunction "VREG_6") (pintype "power_in"))
      (node (ref "U$5") (pin "6") (pinfunction "VREG_6") (pintype "power_in"))
    )
    (net (code "110") (name "VREGISO") (class "Default")
      (node (ref "C11") (pin "1") (pinfunction "1_1") (pintype "passive"))
      (node (ref "C14") (pin "1") (pinfunction "1_1") (pintype "passive"))
      (node (ref "U$5") (pin "15") (pinfunction "VREGISO_15") (pintype "power_in"))
    )
    (net (code "111") (name "VREGISO2") (class "Default")
      (node (ref "C25") (pin "1") (pinfunction "1_1") (pintype "passive"))
      (node (ref "C26") (pin "1") (pinfunction "1_1") (pintype "passive"))
      (node (ref "U$2") (pin "15") (pinfunction "VREGISO_15") (pintype "power_in"))
    )
    (net (code "112") (name "VREGISO2_2") (class "Default")
      (node (ref "C72") (pin "1") (pinfunction "1_1") (pintype "passive"))
      (node (ref "C73") (pin "1") (pinfunction "1_1") (pintype "passive"))
      (node (ref "U$1") (pin "15") (pinfunction "VREGISO_15") (pintype "power_in"))
    )
    (net (code "113") (name "VREGISO_2") (class "Default")
      (node (ref "C50") (pin "1") (pinfunction "1_1") (pintype "passive"))
      (node (ref "C51") (pin "1") (pinfunction "1_1") (pintype "passive"))
      (node (ref "U$3") (pin "15") (pinfunction "VREGISO_15") (pintype "power_in"))
    )
    (net (code "114") (name "VREG_2") (class "Default")
      (node (ref "C59") (pin "1") (pinfunction "1_1") (pintype "passive"))
      (node (ref "C60") (pin "1") (pinfunction "1_1") (pintype "passive"))
      (node (ref "C81") (pin "1") (pinfunction "1_1") (pintype "passive"))
      (node (ref "C82") (pin "1") (pinfunction "1_1") (pintype "passive"))
      (node (ref "SJ10") (pin "1") (pinfunction "1_1") (pintype "passive"))
      (node (ref "SJ4") (pin "1") (pinfunction "1_1") (pintype "passive"))
      (node (ref "U$1") (pin "6") (pinfunction "VREG_6") (pintype "power_in"))
      (node (ref "U$3") (pin "6") (pinfunction "VREG_6") (pintype "power_in"))
    )
    (net (code "115") (name "VSSA") (class "Default")
      (node (ref "IC2") (pin "8") (pinfunction "VSSA_8") (pintype "power_in"))
    )
    (net (code "116") (name "VSS_1") (class "Default")
      (node (ref "IC2") (pin "23") (pinfunction "VSS_1_23") (pintype "power_in"))
    )
    (net (code "117") (name "VSS_2") (class "Default")
      (node (ref "IC2") (pin "35") (pinfunction "VSS_2_35") (pintype "power_in"))
    )
    (net (code "118") (name "VSS_3") (class "Default")
      (node (ref "IC2") (pin "47") (pinfunction "VSS_3_47") (pintype "power_in"))
    )
    (net (code "119") (name "unconnected-(IC2-BOOT0-Pad44)") (class "Default")
      (node (ref "IC2") (pin "44") (pinfunction "BOOT0_44") (pintype "bidirectional"))
    )
    (net (code "120") (name "unconnected-(IC2-NRST-Pad7)") (class "Default")
      (node (ref "IC2") (pin "7") (pinfunction "NRST_7") (pintype "input"))
    )
    (net (code "121") (name "unconnected-(IC2-PA0-WKUP-Pad10)") (class "Default")
      (node (ref "IC2") (pin "10") (pinfunction "PA0-WKUP_10") (pintype "bidirectional"))
    )
    (net (code "122") (name "unconnected-(IC2-PA1-Pad11)") (class "Default")
      (node (ref "IC2") (pin "11") (pinfunction "PA1_11") (pintype "bidirectional"))
    )
    (net (code "123") (name "unconnected-(IC2-PA2-Pad12)") (class "Default")
      (node (ref "IC2") (pin "12") (pinfunction "PA2_12") (pintype "bidirectional"))
    )
    (net (code "124") (name "unconnected-(IC2-PA3-Pad13)") (class "Default")
      (node (ref "IC2") (pin "13") (pinfunction "PA3_13") (pintype "bidirectional"))
    )
    (net (code "125") (name "unconnected-(IC2-PA4-Pad14)") (class "Default")
      (node (ref "IC2") (pin "14") (pinfunction "PA4_14") (pintype "bidirectional"))
    )
    (net (code "126") (name "unconnected-(IC2-PA5-Pad15)") (class "Default")
      (node (ref "IC2") (pin "15") (pinfunction "PA5_15") (pintype "bidirectional"))
    )
    (net (code "127") (name "unconnected-(IC2-PA6-Pad16)") (class "Default")
      (node (ref "IC2") (pin "16") (pinfunction "PA6_16") (pintype "bidirectional"))
    )
    (net (code "128") (name "unconnected-(IC2-PA7-Pad17)") (class "Default")
      (node (ref "IC2") (pin "17") (pinfunction "PA7_17") (pintype "bidirectional"))
    )
    (net (code "129") (name "unconnected-(IC2-PA8-Pad29)") (class "Default")
      (node (ref "IC2") (pin "29") (pinfunction "PA8_29") (pintype "bidirectional"))
    )
    (net (code "130") (name "unconnected-(IC2-PA9-Pad30)") (class "Default")
      (node (ref "IC2") (pin "30") (pinfunction "PA9_30") (pintype "bidirectional"))
    )
    (net (code "131") (name "unconnected-(IC2-PA10-Pad31)") (class "Default")
      (node (ref "IC2") (pin "31") (pinfunction "PA10_31") (pintype "bidirectional"))
    )
    (net (code "132") (name "unconnected-(IC2-PA11-Pad32)") (class "Default")
      (node (ref "IC2") (pin "32") (pinfunction "PA11_32") (pintype "bidirectional"))
    )
    (net (code "133") (name "unconnected-(IC2-PA12-Pad33)") (class "Default")
      (node (ref "IC2") (pin "33") (pinfunction "PA12_33") (pintype "bidirectional"))
    )
    (net (code "134") (name "unconnected-(IC2-PA13-Pad34)") (class "Default")
      (node (ref "IC2") (pin "34") (pinfunction "PA13_34") (pintype "bidirectional"))
    )
    (net (code "135") (name "unconnected-(IC2-PA14-Pad37)") (class "Default")
      (node (ref "IC2") (pin "37") (pinfunction "PA14_37") (pintype "bidirectional"))
    )
    (net (code "136") (name "unconnected-(IC2-PA15-Pad38)") (class "Default")
      (node (ref "IC2") (pin "38") (pinfunction "PA15_38") (pintype "bidirectional"))
    )
    (net (code "137") (name "unconnected-(IC2-PB0-Pad18)") (class "Default")
      (node (ref "IC2") (pin "18") (pinfunction "PB0_18") (pintype "bidirectional"))
    )
    (net (code "138") (name "unconnected-(IC2-PB1-Pad19)") (class "Default")
      (node (ref "IC2") (pin "19") (pinfunction "PB1_19") (pintype "bidirectional"))
    )
    (net (code "139") (name "unconnected-(IC2-PB2-Pad20)") (class "Default")
      (node (ref "IC2") (pin "20") (pinfunction "PB2_20") (pintype "bidirectional"))
    )
    (net (code "140") (name "unconnected-(IC2-PB3-Pad39)") (class "Default")
      (node (ref "IC2") (pin "39") (pinfunction "PB3_39") (pintype "bidirectional"))
    )
    (net (code "141") (name "unconnected-(IC2-PB4-Pad40)") (class "Default")
      (node (ref "IC2") (pin "40") (pinfunction "PB4_40") (pintype "bidirectional"))
    )
    (net (code "142") (name "unconnected-(IC2-PB5-Pad41)") (class "Default")
      (node (ref "IC2") (pin "41") (pinfunction "PB5_41") (pintype "bidirectional"))
    )
    (net (code "143") (name "unconnected-(IC2-PB6-Pad42)") (class "Default")
      (node (ref "IC2") (pin "42") (pinfunction "PB6_42") (pintype "bidirectional"))
    )
    (net (code "144") (name "unconnected-(IC2-PB7-Pad43)") (class "Default")
      (node (ref "IC2") (pin "43") (pinfunction "PB7_43") (pintype "bidirectional"))
    )
    (net (code "145") (name "unconnected-(IC2-PB8-Pad45)") (class "Default")
      (node (ref "IC2") (pin "45") (pinfunction "PB8_45") (pintype "bidirectional"))
    )
    (net (code "146") (name "unconnected-(IC2-PB9-Pad46)") (class "Default")
      (node (ref "IC2") (pin "46") (pinfunction "PB9_46") (pintype "bidirectional"))
    )
    (net (code "147") (name "unconnected-(IC2-PB10-Pad21)") (class "Default")
      (node (ref "IC2") (pin "21") (pinfunction "PB10_21") (pintype "bidirectional"))
    )
    (net (code "148") (name "unconnected-(IC2-PB11-Pad22)") (class "Default")
      (node (ref "IC2") (pin "22") (pinfunction "PB11_22") (pintype "bidirectional"))
    )
    (net (code "149") (name "unconnected-(IC2-PB12-Pad25)") (class "Default")
      (node (ref "IC2") (pin "25") (pinfunction "PB12_25") (pintype "bidirectional"))
    )
    (net (code "150") (name "unconnected-(IC2-PB13-Pad26)") (class "Default")
      (node (ref "IC2") (pin "26") (pinfunction "PB13_26") (pintype "bidirectional"))
    )
    (net (code "151") (name "unconnected-(IC2-PB14-Pad27)") (class "Default")
      (node (ref "IC2") (pin "27") (pinfunction "PB14_27") (pintype "bidirectional"))
    )
    (net (code "152") (name "unconnected-(IC2-PB15-Pad28)") (class "Default")
      (node (ref "IC2") (pin "28") (pinfunction "PB15_28") (pintype "bidirectional"))
    )
    (net (code "153") (name "unconnected-(IC2-PC13-TAMPER-RTC-Pad2)") (class "Default")
      (node (ref "IC2") (pin "2") (pinfunction "PC13-TAMPER-RTC_2") (pintype "bidirectional"))
    )
    (net (code "154") (name "unconnected-(IC2-PC14-OSC32_IN-Pad3)") (class "Default")
      (node (ref "IC2") (pin "3") (pinfunction "PC14-OSC32_IN_3") (pintype "input"))
    )
    (net (code "155") (name "unconnected-(IC2-PC15-OSC32_OUT-Pad4)") (class "Default")
      (node (ref "IC2") (pin "4") (pinfunction "PC15-OSC32_OUT_4") (pintype "output"))
    )
    (net (code "156") (name "unconnected-(IC2-PD0-OSC_IN-Pad5)") (class "Default")
      (node (ref "IC2") (pin "5") (pinfunction "PD0-OSC_IN_5") (pintype "input"))
    )
    (net (code "157") (name "unconnected-(IC2-PD1-OSC_OUT-Pad6)") (class "Default")
      (node (ref "IC2") (pin "6") (pinfunction "PD1-OSC_OUT_6") (pintype "output"))
    )
    (net (code "158") (name "unconnected-(IC2-VBAT-Pad1)") (class "Default")
      (node (ref "IC2") (pin "1") (pinfunction "VBAT_1") (pintype "bidirectional"))
    )
    (net (code "159") (name "unconnected-(IC3-AIO0-Pad30)") (class "Default")
      (node (ref "IC3") (pin "30") (pinfunction "AIO0_30") (pintype "bidirectional"))
    )
    (net (code "160") (name "unconnected-(IC3-AIO1-Pad35)") (class "Default")
      (node (ref "IC3") (pin "35") (pinfunction "AIO1_35") (pintype "bidirectional"))
    )
    (net (code "161") (name "unconnected-(IC3-GND_2-Pad12)") (class "Default")
      (node (ref "IC3") (pin "12") (pinfunction "GND_2_12") (pintype "bidirectional"))
    )
    (net (code "162") (name "unconnected-(IC3-GND_3-Pad28)") (class "Default")
      (node (ref "IC3") (pin "28") (pinfunction "GND_3_28") (pintype "bidirectional"))
    )
    (net (code "163") (name "unconnected-(IC3-GND_4-Pad29)") (class "Default")
      (node (ref "IC3") (pin "29") (pinfunction "GND_4_29") (pintype "bidirectional"))
    )
    (net (code "164") (name "unconnected-(IC3-GPIO2-Pad19)") (class "Default")
      (node (ref "IC3") (pin "19") (pinfunction "GPIO2_19") (pintype "bidirectional"))
    )
    (net (code "165") (name "unconnected-(IC3-GPIO3-Pad20)") (class "Default")
      (node (ref "IC3") (pin "20") (pinfunction "GPIO3_20") (pintype "bidirectional"))
    )
    (net (code "166") (name "unconnected-(IC3-GPIO4-Pad22)") (class "Default")
      (node (ref "IC3") (pin "22") (pinfunction "GPIO4_22") (pintype "bidirectional"))
    )
    (net (code "167") (name "unconnected-(IC3-GPIO5-Pad21)") (class "Default")
      (node (ref "IC3") (pin "21") (pinfunction "GPIO5_21") (pintype "bidirectional"))
    )
    (net (code "168") (name "unconnected-(IC3-GPIO6-Pad3)") (class "Default")
      (node (ref "IC3") (pin "3") (pinfunction "GPIO6_3") (pintype "bidirectional"))
    )
    (net (code "169") (name "unconnected-(IC3-GPIO7-Pad4)") (class "Default")
      (node (ref "IC3") (pin "4") (pinfunction "GPIO7_4") (pintype "bidirectional"))
    )
    (net (code "170") (name "unconnected-(IC3-GPIO8-Pad31)") (class "Default")
      (node (ref "IC3") (pin "31") (pinfunction "GPIO8_31") (pintype "bidirectional"))
    )
    (net (code "171") (name "unconnected-(IC3-GPIO9-Pad32)") (class "Default")
      (node (ref "IC3") (pin "32") (pinfunction "GPIO9_32") (pintype "bidirectional"))
    )
    (net (code "172") (name "unconnected-(IC3-GPIO10-Pad33)") (class "Default")
      (node (ref "IC3") (pin "33") (pinfunction "GPIO10_33") (pintype "bidirectional"))
    )
    (net (code "173") (name "unconnected-(IC3-GPIO11-Pad34)") (class "Default")
      (node (ref "IC3") (pin "34") (pinfunction "GPIO11_34") (pintype "bidirectional"))
    )
    (net (code "174") (name "unconnected-(IC3-MP_1-Pad36)") (class "Default")
      (node (ref "IC3") (pin "36") (pinfunction "MP_1_36") (pintype "bidirectional"))
    )
    (net (code "175") (name "unconnected-(IC3-MP_2-Pad37)") (class "Default")
      (node (ref "IC3") (pin "37") (pinfunction "MP_2_37") (pintype "bidirectional"))
    )
    (net (code "176") (name "unconnected-(IC3-MP_3-Pad38)") (class "Default")
      (node (ref "IC3") (pin "38") (pinfunction "MP_3_38") (pintype "bidirectional"))
    )
    (net (code "177") (name "unconnected-(IC3-MP_4-Pad39)") (class "Default")
      (node (ref "IC3") (pin "39") (pinfunction "MP_4_39") (pintype "bidirectional"))
    )
    (net (code "178") (name "unconnected-(IC3-PCM_CLK-Pad7)") (class "Default")
      (node (ref "IC3") (pin "7") (pinfunction "PCM_CLK_7") (pintype "bidirectional"))
    )
    (net (code "179") (name "unconnected-(IC3-PCM_IN-Pad9)") (class "Default")
      (node (ref "IC3") (pin "9") (pinfunction "PCM_IN_9") (pintype "bidirectional"))
    )
    (net (code "180") (name "unconnected-(IC3-PCM_OUT-Pad10)") (class "Default")
      (node (ref "IC3") (pin "10") (pinfunction "PCM_OUT_10") (pintype "bidirectional"))
    )
    (net (code "181") (name "unconnected-(IC3-PCM_SYNC-Pad8)") (class "Default")
      (node (ref "IC3") (pin "8") (pinfunction "PCM_SYNC_8") (pintype "bidirectional"))
    )
    (net (code "182") (name "unconnected-(IC3-RESET-Pad5)") (class "Default")
      (node (ref "IC3") (pin "5") (pinfunction "RESET_5") (pintype "bidirectional"))
    )
    (net (code "183") (name "unconnected-(IC3-SPI_CLOCK-Pad6)") (class "Default")
      (node (ref "IC3") (pin "6") (pinfunction "SPI_CLOCK_6") (pintype "bidirectional"))
    )
    (net (code "184") (name "unconnected-(IC3-SPI_CSB-Pad23)") (class "Default")
      (node (ref "IC3") (pin "23") (pinfunction "SPI_CSB_23") (pintype "bidirectional"))
    )
    (net (code "185") (name "unconnected-(IC3-SPI_MISO-Pad24)") (class "Default")
      (node (ref "IC3") (pin "24") (pinfunction "SPI_MISO_24") (pintype "bidirectional"))
    )
    (net (code "186") (name "unconnected-(IC3-SPI_MOSI-Pad2)") (class "Default")
      (node (ref "IC3") (pin "2") (pinfunction "SPI_MOSI_2") (pintype "bidirectional"))
    )
    (net (code "187") (name "unconnected-(IC3-UART_CTS-Pad16)") (class "Default")
      (node (ref "IC3") (pin "16") (pinfunction "UART_CTS_16") (pintype "bidirectional"))
    )
    (net (code "188") (name "unconnected-(IC3-UART_RTS-Pad15)") (class "Default")
      (node (ref "IC3") (pin "15") (pinfunction "UART_RTS_15") (pintype "bidirectional"))
    )
    (net (code "189") (name "unconnected-(IC3-UART_RX-Pad13)") (class "Default")
      (node (ref "IC3") (pin "13") (pinfunction "UART_RX_13") (pintype "bidirectional"))
    )
    (net (code "190") (name "unconnected-(IC3-UART_TX-Pad14)") (class "Default")
      (node (ref "IC3") (pin "14") (pinfunction "UART_TX_14") (pintype "bidirectional"))
    )
    (net (code "191") (name "unconnected-(IC3-USB_D+-Pad17)") (class "Default")
      (node (ref "IC3") (pin "17") (pinfunction "USB_D+_17") (pintype "bidirectional"))
    )
    (net (code "192") (name "unconnected-(IC3-USB_D--Pad18)") (class "Default")
      (node (ref "IC3") (pin "18") (pinfunction "USB_D-_18") (pintype "bidirectional"))
    )
    (net (code "193") (name "unconnected-(J1-Pad6)") (class "Default")
      (node (ref "J1") (pin "6") (pinfunction "6_6") (pintype "passive"))
    )
    (net (code "194") (name "unconnected-(J1-Pad7)") (class "Default")
      (node (ref "J1") (pin "7") (pinfunction "7_7") (pintype "passive"))
    )
    (net (code "195") (name "unconnected-(J5-Pad6)") (class "Default")
      (node (ref "J5") (pin "6") (pinfunction "6_6") (pintype "passive"))
    )
    (net (code "196") (name "unconnected-(J5-Pad7)") (class "Default")
      (node (ref "J5") (pin "7") (pinfunction "7_7") (pintype "passive"))
    )
    (net (code "197") (name "unconnected-(X1-B-1-PadB1)") (class "Default")
      (node (ref "X1") (pin "B1") (pinfunction "B-1_B1") (pintype "passive"))
    )
    (net (code "198") (name "unconnected-(X1-B-2-PadB2)") (class "Default")
      (node (ref "X1") (pin "B2") (pinfunction "B-2_B2") (pintype "passive"))
    )
    (net (code "199") (name "unconnected-(X2-B-1-PadB1)") (class "Default")
      (node (ref "X2") (pin "B1") (pinfunction "B-1_B1") (pintype "passive"))
    )
    (net (code "200") (name "unconnected-(X2-B-2-PadB2)") (class "Default")
      (node (ref "X2") (pin "B2") (pinfunction "B-2_B2") (pintype "passive"))
    )
    (net (code "201") (name "unconnected-(X3-B-1-PadB1)") (class "Default")
      (node (ref "X3") (pin "B1") (pinfunction "B-1_B1") (pintype "passive"))
    )
    (net (code "202") (name "unconnected-(X3-B-2-PadB2)") (class "Default")
      (node (ref "X3") (pin "B2") (pinfunction "B-2_B2") (pintype "passive"))
    )
    (net (code "203") (name "unconnected-(X4-B-1-PadB1)") (class "Default")
      (node (ref "X4") (pin "B1") (pinfunction "B-1_B1") (pintype "passive"))
    )
    (net (code "204") (name "unconnected-(X4-B-2-PadB2)") (class "Default")
      (node (ref "X4") (pin "B2") (pinfunction "B-2_B2") (pintype "passive"))
    )
    (net (code "205") (name "unconnected-(X5-B-1-PadB1)") (class "Default")
      (node (ref "X5") (pin "B1") (pinfunction "B-1_B1") (pintype "passive"))
    )
    (net (code "206") (name "unconnected-(X5-B-2-PadB2)") (class "Default")
      (node (ref "X5") (pin "B2") (pinfunction "B-2_B2") (pintype "passive"))
    )
    (net (code "207") (name "unconnected-(X6-B-1-PadB1)") (class "Default")
      (node (ref "X6") (pin "B1") (pinfunction "B-1_B1") (pintype "passive"))
    )
    (net (code "208") (name "unconnected-(X6-B-2-PadB2)") (class "Default")
      (node (ref "X6") (pin "B2") (pinfunction "B-2_B2") (pintype "passive"))
    )
    (net (code "209") (name "{slash}DIAG1") (class "Default")
      (node (ref "DL2") (pin "C") (pinfunction "C_C") (pintype "passive"))
      (node (ref "J1") (pin "3") (pinfunction "3_3") (pintype "passive"))
      (node (ref "U$5") (pin "10") (pinfunction "/DIAG1_10") (pintype "output"))
    )
    (net (code "210") (name "{slash}DIAG1_2") (class "Default")
      (node (ref "DL6") (pin "C") (pinfunction "C_C") (pintype "passive"))
      (node (ref "J5") (pin "3") (pinfunction "3_3") (pintype "passive"))
      (node (ref "U$3") (pin "10") (pinfunction "/DIAG1_10") (pintype "output"))
    )
    (net (code "211") (name "{slash}DIAG12") (class "Default")
      (node (ref "DL4") (pin "C") (pinfunction "C_C") (pintype "passive"))
      (node (ref "J2") (pin "2") (pinfunction "2_2") (pintype "passive"))
      (node (ref "U$2") (pin "10") (pinfunction "/DIAG1_10") (pintype "output"))
    )
    (net (code "212") (name "{slash}DIAG12_2") (class "Default")
      (node (ref "DL8") (pin "C") (pinfunction "C_C") (pintype "passive"))
      (node (ref "J6") (pin "2") (pinfunction "2_2") (pintype "passive"))
      (node (ref "U$1") (pin "10") (pinfunction "/DIAG1_10") (pintype "output"))
    )
  )
)
